# S7500_Drv.net
KiCad netlist of a schematic drawn in Altium Designer
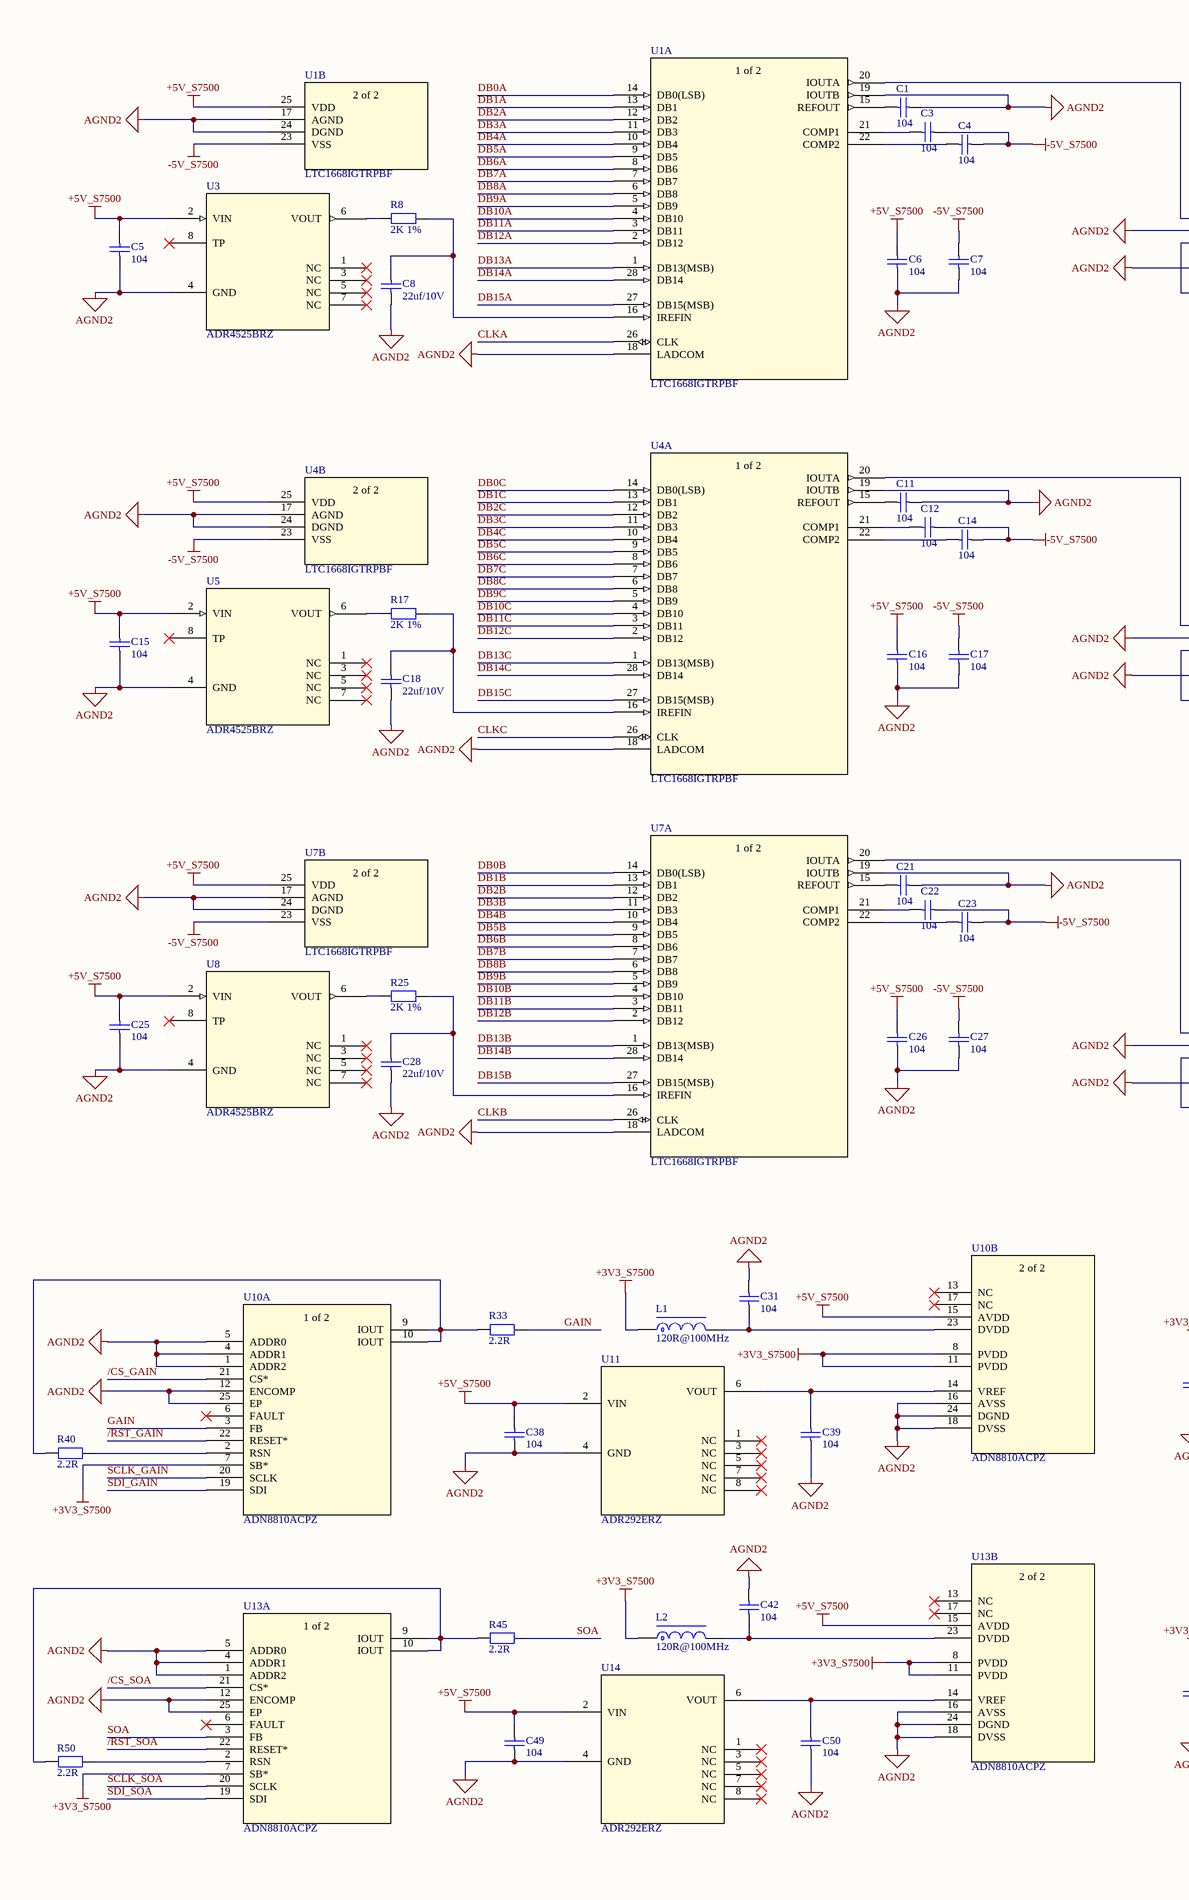
[diagram p0: S7500_Drv.SchDoc, left]
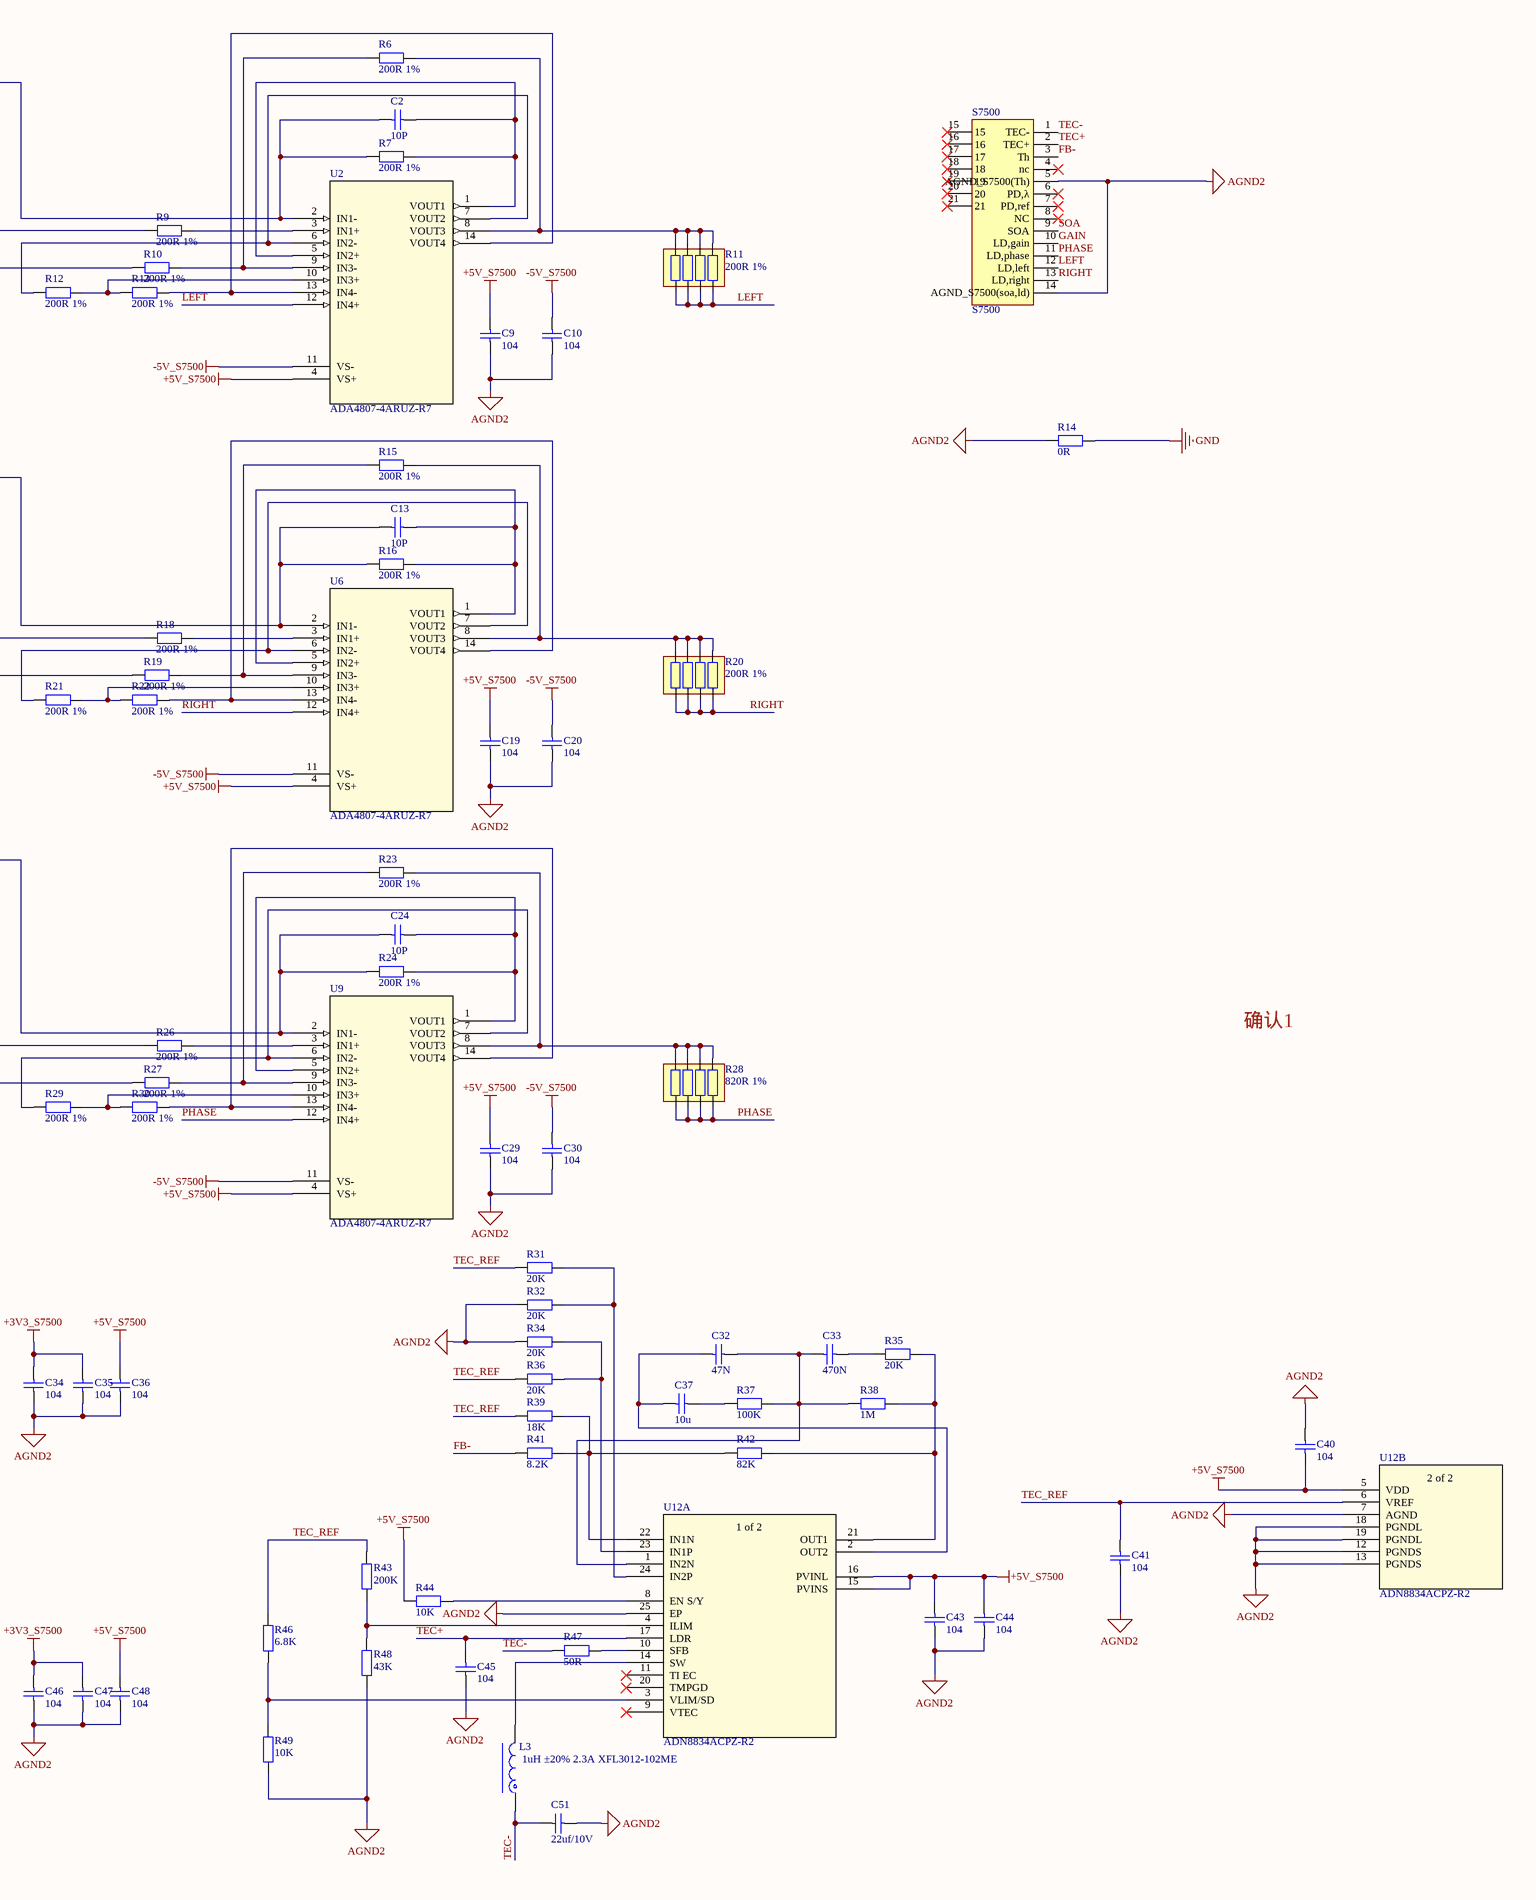
[diagram p1: S7500_Drv.SchDoc, right]

(export (version "E")
  (design (tool "Eeschema 10.0.6"))
  (components
    (comp (ref "C1")
      (value "104")
      (footprint "C0402_L")
      (description "贴片电容/MLCC电容")
      (libsource (lib "0.1 - 电阻-电容-电感-保险丝-晶振-晶体-磁珠-电位器-法拉电容-馈通电容") (part "C"))
    )
    (comp (ref "C2")
      (value "10P")
      (footprint "C0402_L")
      (description "贴片电容/MLCC电容")
      (libsource (lib "0.1 - 电阻-电容-电感-保险丝-晶振-晶体-磁珠-电位器-法拉电容-馈通电容") (part "C"))
    )
    (comp (ref "C3")
      (value "104")
      (footprint "C0402_L")
      (description "贴片电容/MLCC电容")
      (libsource (lib "0.1 - 电阻-电容-电感-保险丝-晶振-晶体-磁珠-电位器-法拉电容-馈通电容") (part "C"))
    )
    (comp (ref "C4")
      (value "104")
      (footprint "C0402_L")
      (description "贴片电容/MLCC电容")
      (libsource (lib "0.1 - 电阻-电容-电感-保险丝-晶振-晶体-磁珠-电位器-法拉电容-馈通电容") (part "C"))
    )
    (comp (ref "C5")
      (value "104")
      (footprint "C0402_L")
      (description "贴片电容/MLCC电容")
      (libsource (lib "0.1 - 电阻-电容-电感-保险丝-晶振-晶体-磁珠-电位器-法拉电容-馈通电容") (part "C"))
    )
    (comp (ref "C6")
      (value "104")
      (footprint "C0402_L")
      (description "贴片电容/MLCC电容")
      (libsource (lib "0.1 - 电阻-电容-电感-保险丝-晶振-晶体-磁珠-电位器-法拉电容-馈通电容") (part "C"))
    )
    (comp (ref "C7")
      (value "104")
      (footprint "C0402_L")
      (description "贴片电容/MLCC电容")
      (libsource (lib "0.1 - 电阻-电容-电感-保险丝-晶振-晶体-磁珠-电位器-法拉电容-馈通电容") (part "C"))
    )
    (comp (ref "C8")
      (value "22uf/10V")
      (footprint "C0402_L")
      (description "贴片电容/MLCC电容")
      (libsource (lib "0.1 - 电阻-电容-电感-保险丝-晶振-晶体-磁珠-电位器-法拉电容-馈通电容") (part "C"))
    )
    (comp (ref "C9")
      (value "104")
      (footprint "C0402_L")
      (description "贴片电容/MLCC电容")
      (libsource (lib "0.1 - 电阻-电容-电感-保险丝-晶振-晶体-磁珠-电位器-法拉电容-馈通电容") (part "C"))
    )
    (comp (ref "C10")
      (value "104")
      (footprint "C0402_L")
      (description "贴片电容/MLCC电容")
      (libsource (lib "0.1 - 电阻-电容-电感-保险丝-晶振-晶体-磁珠-电位器-法拉电容-馈通电容") (part "C"))
    )
    (comp (ref "C11")
      (value "104")
      (footprint "C0402_L")
      (description "贴片电容/MLCC电容")
      (libsource (lib "0.1 - 电阻-电容-电感-保险丝-晶振-晶体-磁珠-电位器-法拉电容-馈通电容") (part "C"))
    )
    (comp (ref "C12")
      (value "104")
      (footprint "C0402_L")
      (description "贴片电容/MLCC电容")
      (libsource (lib "0.1 - 电阻-电容-电感-保险丝-晶振-晶体-磁珠-电位器-法拉电容-馈通电容") (part "C"))
    )
    (comp (ref "C13")
      (value "10P")
      (footprint "C0402_L")
      (description "贴片电容/MLCC电容")
      (libsource (lib "0.1 - 电阻-电容-电感-保险丝-晶振-晶体-磁珠-电位器-法拉电容-馈通电容") (part "C"))
    )
    (comp (ref "C14")
      (value "104")
      (footprint "C0402_L")
      (description "贴片电容/MLCC电容")
      (libsource (lib "0.1 - 电阻-电容-电感-保险丝-晶振-晶体-磁珠-电位器-法拉电容-馈通电容") (part "C"))
    )
    (comp (ref "C15")
      (value "104")
      (footprint "C0402_L")
      (description "贴片电容/MLCC电容")
      (libsource (lib "0.1 - 电阻-电容-电感-保险丝-晶振-晶体-磁珠-电位器-法拉电容-馈通电容") (part "C"))
    )
    (comp (ref "C16")
      (value "104")
      (footprint "C0402_L")
      (description "贴片电容/MLCC电容")
      (libsource (lib "0.1 - 电阻-电容-电感-保险丝-晶振-晶体-磁珠-电位器-法拉电容-馈通电容") (part "C"))
    )
    (comp (ref "C17")
      (value "104")
      (footprint "C0402_L")
      (description "贴片电容/MLCC电容")
      (libsource (lib "0.1 - 电阻-电容-电感-保险丝-晶振-晶体-磁珠-电位器-法拉电容-馈通电容") (part "C"))
    )
    (comp (ref "C18")
      (value "22uf/10V")
      (footprint "C0402_L")
      (description "贴片电容/MLCC电容")
      (libsource (lib "0.1 - 电阻-电容-电感-保险丝-晶振-晶体-磁珠-电位器-法拉电容-馈通电容") (part "C"))
    )
    (comp (ref "C19")
      (value "104")
      (footprint "C0402_L")
      (description "贴片电容/MLCC电容")
      (libsource (lib "0.1 - 电阻-电容-电感-保险丝-晶振-晶体-磁珠-电位器-法拉电容-馈通电容") (part "C"))
    )
    (comp (ref "C20")
      (value "104")
      (footprint "C0402_L")
      (description "贴片电容/MLCC电容")
      (libsource (lib "0.1 - 电阻-电容-电感-保险丝-晶振-晶体-磁珠-电位器-法拉电容-馈通电容") (part "C"))
    )
    (comp (ref "C21")
      (value "104")
      (footprint "C0402_L")
      (description "贴片电容/MLCC电容")
      (libsource (lib "0.1 - 电阻-电容-电感-保险丝-晶振-晶体-磁珠-电位器-法拉电容-馈通电容") (part "C"))
    )
    (comp (ref "C22")
      (value "104")
      (footprint "C0402_L")
      (description "贴片电容/MLCC电容")
      (libsource (lib "0.1 - 电阻-电容-电感-保险丝-晶振-晶体-磁珠-电位器-法拉电容-馈通电容") (part "C"))
    )
    (comp (ref "C23")
      (value "104")
      (footprint "C0402_L")
      (description "贴片电容/MLCC电容")
      (libsource (lib "0.1 - 电阻-电容-电感-保险丝-晶振-晶体-磁珠-电位器-法拉电容-馈通电容") (part "C"))
    )
    (comp (ref "C24")
      (value "10P")
      (footprint "C0402_L")
      (description "贴片电容/MLCC电容")
      (libsource (lib "0.1 - 电阻-电容-电感-保险丝-晶振-晶体-磁珠-电位器-法拉电容-馈通电容") (part "C"))
    )
    (comp (ref "C25")
      (value "104")
      (footprint "C0402_L")
      (description "贴片电容/MLCC电容")
      (libsource (lib "0.1 - 电阻-电容-电感-保险丝-晶振-晶体-磁珠-电位器-法拉电容-馈通电容") (part "C"))
    )
    (comp (ref "C26")
      (value "104")
      (footprint "C0402_L")
      (description "贴片电容/MLCC电容")
      (libsource (lib "0.1 - 电阻-电容-电感-保险丝-晶振-晶体-磁珠-电位器-法拉电容-馈通电容") (part "C"))
    )
    (comp (ref "C27")
      (value "104")
      (footprint "C0402_L")
      (description "贴片电容/MLCC电容")
      (libsource (lib "0.1 - 电阻-电容-电感-保险丝-晶振-晶体-磁珠-电位器-法拉电容-馈通电容") (part "C"))
    )
    (comp (ref "C28")
      (value "22uf/10V")
      (footprint "C0402_L")
      (description "贴片电容/MLCC电容")
      (libsource (lib "0.1 - 电阻-电容-电感-保险丝-晶振-晶体-磁珠-电位器-法拉电容-馈通电容") (part "C"))
    )
    (comp (ref "C29")
      (value "104")
      (footprint "C0402_L")
      (description "贴片电容/MLCC电容")
      (libsource (lib "0.1 - 电阻-电容-电感-保险丝-晶振-晶体-磁珠-电位器-法拉电容-馈通电容") (part "C"))
    )
    (comp (ref "C30")
      (value "104")
      (footprint "C0402_L")
      (description "贴片电容/MLCC电容")
      (libsource (lib "0.1 - 电阻-电容-电感-保险丝-晶振-晶体-磁珠-电位器-法拉电容-馈通电容") (part "C"))
    )
    (comp (ref "C31")
      (value "104")
      (footprint "C0402_L")
      (description "贴片电容/MLCC电容")
      (libsource (lib "0.1 - 电阻-电容-电感-保险丝-晶振-晶体-磁珠-电位器-法拉电容-馈通电容") (part "C"))
    )
    (comp (ref "C32")
      (value "47N")
      (footprint "C0402_L")
      (description "贴片电容/MLCC电容")
      (libsource (lib "0.1 - 电阻-电容-电感-保险丝-晶振-晶体-磁珠-电位器-法拉电容-馈通电容") (part "C"))
    )
    (comp (ref "C33")
      (value "470N")
      (footprint "C0402_L")
      (description "贴片电容/MLCC电容")
      (libsource (lib "0.1 - 电阻-电容-电感-保险丝-晶振-晶体-磁珠-电位器-法拉电容-馈通电容") (part "C"))
    )
    (comp (ref "C34")
      (value "104")
      (footprint "C0402_L")
      (description "贴片电容/MLCC电容")
      (libsource (lib "0.1 - 电阻-电容-电感-保险丝-晶振-晶体-磁珠-电位器-法拉电容-馈通电容") (part "C"))
    )
    (comp (ref "C35")
      (value "104")
      (footprint "C0402_L")
      (description "贴片电容/MLCC电容")
      (libsource (lib "0.1 - 电阻-电容-电感-保险丝-晶振-晶体-磁珠-电位器-法拉电容-馈通电容") (part "C"))
    )
    (comp (ref "C36")
      (value "104")
      (footprint "C0402_L")
      (description "贴片电容/MLCC电容")
      (libsource (lib "0.1 - 电阻-电容-电感-保险丝-晶振-晶体-磁珠-电位器-法拉电容-馈通电容") (part "C"))
    )
    (comp (ref "C37")
      (value "10u")
      (footprint "C0402_L")
      (description "贴片电容/MLCC电容")
      (libsource (lib "0.1 - 电阻-电容-电感-保险丝-晶振-晶体-磁珠-电位器-法拉电容-馈通电容") (part "C"))
    )
    (comp (ref "C38")
      (value "104")
      (footprint "C0402_L")
      (description "贴片电容/MLCC电容")
      (libsource (lib "0.1 - 电阻-电容-电感-保险丝-晶振-晶体-磁珠-电位器-法拉电容-馈通电容") (part "C"))
    )
    (comp (ref "C39")
      (value "104")
      (footprint "C0402_L")
      (description "贴片电容/MLCC电容")
      (libsource (lib "0.1 - 电阻-电容-电感-保险丝-晶振-晶体-磁珠-电位器-法拉电容-馈通电容") (part "C"))
    )
    (comp (ref "C40")
      (value "104")
      (footprint "C0402_L")
      (description "贴片电容/MLCC电容")
      (libsource (lib "0.1 - 电阻-电容-电感-保险丝-晶振-晶体-磁珠-电位器-法拉电容-馈通电容") (part "C"))
    )
    (comp (ref "C41")
      (value "104")
      (footprint "C0402_L")
      (description "贴片电容/MLCC电容")
      (libsource (lib "0.1 - 电阻-电容-电感-保险丝-晶振-晶体-磁珠-电位器-法拉电容-馈通电容") (part "C"))
    )
    (comp (ref "C42")
      (value "104")
      (footprint "C0402_L")
      (description "贴片电容/MLCC电容")
      (libsource (lib "0.1 - 电阻-电容-电感-保险丝-晶振-晶体-磁珠-电位器-法拉电容-馈通电容") (part "C"))
    )
    (comp (ref "C43")
      (value "104")
      (footprint "C0402_L")
      (description "贴片电容/MLCC电容")
      (libsource (lib "0.1 - 电阻-电容-电感-保险丝-晶振-晶体-磁珠-电位器-法拉电容-馈通电容") (part "C"))
    )
    (comp (ref "C44")
      (value "104")
      (footprint "C0402_L")
      (description "贴片电容/MLCC电容")
      (libsource (lib "0.1 - 电阻-电容-电感-保险丝-晶振-晶体-磁珠-电位器-法拉电容-馈通电容") (part "C"))
    )
    (comp (ref "C45")
      (value "104")
      (footprint "C0402_L")
      (description "贴片电容/MLCC电容")
      (libsource (lib "0.1 - 电阻-电容-电感-保险丝-晶振-晶体-磁珠-电位器-法拉电容-馈通电容") (part "C"))
    )
    (comp (ref "C46")
      (value "104")
      (footprint "C0402_L")
      (description "贴片电容/MLCC电容")
      (libsource (lib "0.1 - 电阻-电容-电感-保险丝-晶振-晶体-磁珠-电位器-法拉电容-馈通电容") (part "C"))
    )
    (comp (ref "C47")
      (value "104")
      (footprint "C0402_L")
      (description "贴片电容/MLCC电容")
      (libsource (lib "0.1 - 电阻-电容-电感-保险丝-晶振-晶体-磁珠-电位器-法拉电容-馈通电容") (part "C"))
    )
    (comp (ref "C48")
      (value "104")
      (footprint "C0402_L")
      (description "贴片电容/MLCC电容")
      (libsource (lib "0.1 - 电阻-电容-电感-保险丝-晶振-晶体-磁珠-电位器-法拉电容-馈通电容") (part "C"))
    )
    (comp (ref "C49")
      (value "104")
      (footprint "C0402_L")
      (description "贴片电容/MLCC电容")
      (libsource (lib "0.1 - 电阻-电容-电感-保险丝-晶振-晶体-磁珠-电位器-法拉电容-馈通电容") (part "C"))
    )
    (comp (ref "C50")
      (value "104")
      (footprint "C0402_L")
      (description "贴片电容/MLCC电容")
      (libsource (lib "0.1 - 电阻-电容-电感-保险丝-晶振-晶体-磁珠-电位器-法拉电容-馈通电容") (part "C"))
    )
    (comp (ref "C51")
      (value "22uf/10V")
      (footprint "C0402_L")
      (description "贴片电容/MLCC电容")
      (libsource (lib "0.1 - 电阻-电容-电感-保险丝-晶振-晶体-磁珠-电位器-法拉电容-馈通电容") (part "C"))
    )
    (comp (ref "L1")
      (value "120R@100MHz")
      (footprint "FB0402")
      (description "贴片磁珠")
      (libsource (lib "0.1 - 电阻-电容-电感-保险丝-晶振-晶体-磁珠-电位器-法拉电容-馈通电容") (part "FB"))
    )
    (comp (ref "L2")
      (value "120R@100MHz")
      (footprint "FB0402")
      (description "贴片磁珠")
      (libsource (lib "0.1 - 电阻-电容-电感-保险丝-晶振-晶体-磁珠-电位器-法拉电容-馈通电容") (part "FB"))
    )
    (comp (ref "L3")
      (value "1uH ±20% 2.3A XFL3012-102ME")
      (footprint "SWPA3015")
      (description "顺络_SWPA贴片屏蔽电感")
      (libsource (lib "0.1 - 电阻-电容-电感-保险丝-晶振-晶体-磁珠-电位器-法拉电容-馈通电容") (part "L-SWPA"))
    )
    (comp (ref "R6")
      (value "200R 1%")
      (footprint "R0402_L")
      (description "贴片电阻")
      (libsource (lib "0.1 - 电阻-电容-电感-保险丝-晶振-晶体-磁珠-电位器-法拉电容-馈通电容") (part "R"))
    )
    (comp (ref "R7")
      (value "200R 1%")
      (footprint "R0402_L")
      (description "贴片电阻")
      (libsource (lib "0.1 - 电阻-电容-电感-保险丝-晶振-晶体-磁珠-电位器-法拉电容-馈通电容") (part "R"))
    )
    (comp (ref "R8")
      (value "2K 1%")
      (footprint "R0402_L")
      (description "贴片电阻")
      (libsource (lib "0.1 - 电阻-电容-电感-保险丝-晶振-晶体-磁珠-电位器-法拉电容-馈通电容") (part "R"))
    )
    (comp (ref "R9")
      (value "200R 1%")
      (footprint "R0402_L")
      (description "贴片电阻")
      (libsource (lib "0.1 - 电阻-电容-电感-保险丝-晶振-晶体-磁珠-电位器-法拉电容-馈通电容") (part "R"))
    )
    (comp (ref "R10")
      (value "200R 1%")
      (footprint "R0402_L")
      (description "贴片电阻")
      (libsource (lib "0.1 - 电阻-电容-电感-保险丝-晶振-晶体-磁珠-电位器-法拉电容-馈通电容") (part "R"))
    )
    (comp (ref "R11")
      (value "200R 1%")
      (footprint "RCA-8P4R-0603")
      (description "贴片4P排阻")
      (libsource (lib "0.1 - 电阻-电容-电感-保险丝-晶振-晶体-磁珠-电位器-法拉电容-馈通电容") (part "R-8P4R"))
    )
    (comp (ref "R12")
      (value "200R 1%")
      (footprint "R0402_L")
      (description "贴片电阻")
      (libsource (lib "0.1 - 电阻-电容-电感-保险丝-晶振-晶体-磁珠-电位器-法拉电容-馈通电容") (part "R"))
    )
    (comp (ref "R13")
      (value "200R 1%")
      (footprint "R0402_L")
      (description "贴片电阻")
      (libsource (lib "0.1 - 电阻-电容-电感-保险丝-晶振-晶体-磁珠-电位器-法拉电容-馈通电容") (part "R"))
    )
    (comp (ref "R14")
      (value "0R")
      (footprint "R0402_L")
      (description "贴片电阻")
      (libsource (lib "0.1 - 电阻-电容-电感-保险丝-晶振-晶体-磁珠-电位器-法拉电容-馈通电容") (part "R"))
    )
    (comp (ref "R15")
      (value "200R 1%")
      (footprint "R0402_L")
      (description "贴片电阻")
      (libsource (lib "0.1 - 电阻-电容-电感-保险丝-晶振-晶体-磁珠-电位器-法拉电容-馈通电容") (part "R"))
    )
    (comp (ref "R16")
      (value "200R 1%")
      (footprint "R0402_L")
      (description "贴片电阻")
      (libsource (lib "0.1 - 电阻-电容-电感-保险丝-晶振-晶体-磁珠-电位器-法拉电容-馈通电容") (part "R"))
    )
    (comp (ref "R17")
      (value "2K 1%")
      (footprint "R0402_L")
      (description "贴片电阻")
      (libsource (lib "0.1 - 电阻-电容-电感-保险丝-晶振-晶体-磁珠-电位器-法拉电容-馈通电容") (part "R"))
    )
    (comp (ref "R18")
      (value "200R 1%")
      (footprint "R0402_L")
      (description "贴片电阻")
      (libsource (lib "0.1 - 电阻-电容-电感-保险丝-晶振-晶体-磁珠-电位器-法拉电容-馈通电容") (part "R"))
    )
    (comp (ref "R19")
      (value "200R 1%")
      (footprint "R0402_L")
      (description "贴片电阻")
      (libsource (lib "0.1 - 电阻-电容-电感-保险丝-晶振-晶体-磁珠-电位器-法拉电容-馈通电容") (part "R"))
    )
    (comp (ref "R20")
      (value "200R 1%")
      (footprint "RCA-8P4R-0603")
      (description "贴片4P排阻")
      (libsource (lib "0.1 - 电阻-电容-电感-保险丝-晶振-晶体-磁珠-电位器-法拉电容-馈通电容") (part "R-8P4R"))
    )
    (comp (ref "R21")
      (value "200R 1%")
      (footprint "R0402_L")
      (description "贴片电阻")
      (libsource (lib "0.1 - 电阻-电容-电感-保险丝-晶振-晶体-磁珠-电位器-法拉电容-馈通电容") (part "R"))
    )
    (comp (ref "R22")
      (value "200R 1%")
      (footprint "R0402_L")
      (description "贴片电阻")
      (libsource (lib "0.1 - 电阻-电容-电感-保险丝-晶振-晶体-磁珠-电位器-法拉电容-馈通电容") (part "R"))
    )
    (comp (ref "R23")
      (value "200R 1%")
      (footprint "R0402_L")
      (description "贴片电阻")
      (libsource (lib "0.1 - 电阻-电容-电感-保险丝-晶振-晶体-磁珠-电位器-法拉电容-馈通电容") (part "R"))
    )
    (comp (ref "R24")
      (value "200R 1%")
      (footprint "R0402_L")
      (description "贴片电阻")
      (libsource (lib "0.1 - 电阻-电容-电感-保险丝-晶振-晶体-磁珠-电位器-法拉电容-馈通电容") (part "R"))
    )
    (comp (ref "R25")
      (value "2K 1%")
      (footprint "R0402_L")
      (description "贴片电阻")
      (libsource (lib "0.1 - 电阻-电容-电感-保险丝-晶振-晶体-磁珠-电位器-法拉电容-馈通电容") (part "R"))
    )
    (comp (ref "R26")
      (value "200R 1%")
      (footprint "R0402_L")
      (description "贴片电阻")
      (libsource (lib "0.1 - 电阻-电容-电感-保险丝-晶振-晶体-磁珠-电位器-法拉电容-馈通电容") (part "R"))
    )
    (comp (ref "R27")
      (value "200R 1%")
      (footprint "R0402_L")
      (description "贴片电阻")
      (libsource (lib "0.1 - 电阻-电容-电感-保险丝-晶振-晶体-磁珠-电位器-法拉电容-馈通电容") (part "R"))
    )
    (comp (ref "R28")
      (value "820R 1%")
      (footprint "RCA-8P4R-0603")
      (description "贴片4P排阻")
      (libsource (lib "0.1 - 电阻-电容-电感-保险丝-晶振-晶体-磁珠-电位器-法拉电容-馈通电容") (part "R-8P4R"))
    )
    (comp (ref "R29")
      (value "200R 1%")
      (footprint "R0402_L")
      (description "贴片电阻")
      (libsource (lib "0.1 - 电阻-电容-电感-保险丝-晶振-晶体-磁珠-电位器-法拉电容-馈通电容") (part "R"))
    )
    (comp (ref "R30")
      (value "200R 1%")
      (footprint "R0402_L")
      (description "贴片电阻")
      (libsource (lib "0.1 - 电阻-电容-电感-保险丝-晶振-晶体-磁珠-电位器-法拉电容-馈通电容") (part "R"))
    )
    (comp (ref "R31")
      (value "20K")
      (footprint "R0402_L")
      (description "贴片电阻")
      (libsource (lib "0.1 - 电阻-电容-电感-保险丝-晶振-晶体-磁珠-电位器-法拉电容-馈通电容") (part "R"))
    )
    (comp (ref "R32")
      (value "20K")
      (footprint "R0402_L")
      (description "贴片电阻")
      (libsource (lib "0.1 - 电阻-电容-电感-保险丝-晶振-晶体-磁珠-电位器-法拉电容-馈通电容") (part "R"))
    )
    (comp (ref "R33")
      (value "2.2R")
      (footprint "R0603_L")
      (description "贴片电阻")
      (libsource (lib "0.1 - 电阻-电容-电感-保险丝-晶振-晶体-磁珠-电位器-法拉电容-馈通电容") (part "R"))
    )
    (comp (ref "R34")
      (value "20K")
      (footprint "R0402_L")
      (description "贴片电阻")
      (libsource (lib "0.1 - 电阻-电容-电感-保险丝-晶振-晶体-磁珠-电位器-法拉电容-馈通电容") (part "R"))
    )
    (comp (ref "R35")
      (value "20K")
      (footprint "R0402_L")
      (description "贴片电阻")
      (libsource (lib "0.1 - 电阻-电容-电感-保险丝-晶振-晶体-磁珠-电位器-法拉电容-馈通电容") (part "R"))
    )
    (comp (ref "R36")
      (value "20K")
      (footprint "R0402_L")
      (description "贴片电阻")
      (libsource (lib "0.1 - 电阻-电容-电感-保险丝-晶振-晶体-磁珠-电位器-法拉电容-馈通电容") (part "R"))
    )
    (comp (ref "R37")
      (value "100K")
      (footprint "R0402_L")
      (description "贴片电阻")
      (libsource (lib "0.1 - 电阻-电容-电感-保险丝-晶振-晶体-磁珠-电位器-法拉电容-馈通电容") (part "R"))
    )
    (comp (ref "R38")
      (value "1M")
      (footprint "R0402_L")
      (description "贴片电阻")
      (libsource (lib "0.1 - 电阻-电容-电感-保险丝-晶振-晶体-磁珠-电位器-法拉电容-馈通电容") (part "R"))
    )
    (comp (ref "R39")
      (value "18K")
      (footprint "R0402_L")
      (description "贴片电阻")
      (libsource (lib "0.1 - 电阻-电容-电感-保险丝-晶振-晶体-磁珠-电位器-法拉电容-馈通电容") (part "R"))
    )
    (comp (ref "R40")
      (value "2.2R")
      (footprint "R0603_L")
      (description "贴片电阻")
      (libsource (lib "0.1 - 电阻-电容-电感-保险丝-晶振-晶体-磁珠-电位器-法拉电容-馈通电容") (part "R"))
    )
    (comp (ref "R41")
      (value "8.2K")
      (footprint "R0402_L")
      (description "贴片电阻")
      (libsource (lib "0.1 - 电阻-电容-电感-保险丝-晶振-晶体-磁珠-电位器-法拉电容-馈通电容") (part "R"))
    )
    (comp (ref "R42")
      (value "82K")
      (footprint "R0402_L")
      (description "贴片电阻")
      (libsource (lib "0.1 - 电阻-电容-电感-保险丝-晶振-晶体-磁珠-电位器-法拉电容-馈通电容") (part "R"))
    )
    (comp (ref "R43")
      (value "200K")
      (footprint "R0402_L")
      (description "贴片电阻")
      (libsource (lib "0.1 - 电阻-电容-电感-保险丝-晶振-晶体-磁珠-电位器-法拉电容-馈通电容") (part "R"))
    )
    (comp (ref "R44")
      (value "10K")
      (footprint "R0402_L")
      (description "贴片电阻")
      (libsource (lib "0.1 - 电阻-电容-电感-保险丝-晶振-晶体-磁珠-电位器-法拉电容-馈通电容") (part "R"))
    )
    (comp (ref "R45")
      (value "2.2R")
      (footprint "R0603_L")
      (description "贴片电阻")
      (libsource (lib "0.1 - 电阻-电容-电感-保险丝-晶振-晶体-磁珠-电位器-法拉电容-馈通电容") (part "R"))
    )
    (comp (ref "R46")
      (value "6.8K")
      (footprint "R0402_L")
      (description "贴片电阻")
      (libsource (lib "0.1 - 电阻-电容-电感-保险丝-晶振-晶体-磁珠-电位器-法拉电容-馈通电容") (part "R"))
    )
    (comp (ref "R47")
      (value "50R")
      (footprint "R0402_L")
      (description "贴片电阻")
      (libsource (lib "0.1 - 电阻-电容-电感-保险丝-晶振-晶体-磁珠-电位器-法拉电容-馈通电容") (part "R"))
    )
    (comp (ref "R48")
      (value "43K")
      (footprint "R0402_L")
      (description "贴片电阻")
      (libsource (lib "0.1 - 电阻-电容-电感-保险丝-晶振-晶体-磁珠-电位器-法拉电容-馈通电容") (part "R"))
    )
    (comp (ref "R49")
      (value "10K")
      (footprint "R0402_L")
      (description "贴片电阻")
      (libsource (lib "0.1 - 电阻-电容-电感-保险丝-晶振-晶体-磁珠-电位器-法拉电容-馈通电容") (part "R"))
    )
    (comp (ref "R50")
      (value "2.2R")
      (footprint "R0603_L")
      (description "贴片电阻")
      (libsource (lib "0.1 - 电阻-电容-电感-保险丝-晶振-晶体-磁珠-电位器-法拉电容-馈通电容") (part "R"))
    )
    (comp (ref "S7500")
      (value "S7500")
      (footprint "S7500-14*0.8mm")
      (libsource (lib "PCB_Project") (part "S7500"))
    )
    (comp (ref "U1")
      (value "LTC1668IGTRPBF")
      (footprint "SSOP-28_G_LIT")
      (description "No Description Available")
      (libsource (lib "LTC1668IGTRPBF") (part "LTC1668IGTRPBF"))
    )
    (comp (ref "U2")
      (value "ADA4807-4ARUZ-R7")
      (footprint "RU-14_ADI")
      (description "No Description Available")
      (libsource (lib "ADA4807-4ARUZ-R7") (part "ADA4807-4ARUZ-R7"))
    )
    (comp (ref "U3")
      (value "ADR4525BRZ")
      (footprint "R_8_ADI")
      (description "No Description Available")
      (libsource (lib "ADR4525BRZ") (part "ADR4525BRZ"))
    )
    (comp (ref "U4")
      (value "LTC1668IGTRPBF")
      (footprint "SSOP-28_G_LIT")
      (description "No Description Available")
      (libsource (lib "LTC1668IGTRPBF") (part "LTC1668IGTRPBF"))
    )
    (comp (ref "U5")
      (value "ADR4525BRZ")
      (footprint "R_8_ADI")
      (description "No Description Available")
      (libsource (lib "ADR4525BRZ") (part "ADR4525BRZ"))
    )
    (comp (ref "U6")
      (value "ADA4807-4ARUZ-R7")
      (footprint "RU-14_ADI")
      (description "No Description Available")
      (libsource (lib "ADA4807-4ARUZ-R7") (part "ADA4807-4ARUZ-R7"))
    )
    (comp (ref "U7")
      (value "LTC1668IGTRPBF")
      (footprint "SSOP-28_G_LIT")
      (description "No Description Available")
      (libsource (lib "LTC1668IGTRPBF") (part "LTC1668IGTRPBF"))
    )
    (comp (ref "U8")
      (value "ADR4525BRZ")
      (footprint "R_8_ADI")
      (description "No Description Available")
      (libsource (lib "ADR4525BRZ") (part "ADR4525BRZ"))
    )
    (comp (ref "U9")
      (value "ADA4807-4ARUZ-R7")
      (footprint "RU-14_ADI")
      (description "No Description Available")
      (libsource (lib "ADA4807-4ARUZ-R7") (part "ADA4807-4ARUZ-R7"))
    )
    (comp (ref "U10")
      (value "ADN8810ACPZ")
      (footprint "CP_24_1_ADI")
      (description "No Description Available")
      (libsource (lib "ADN8810ACPZ") (part "ADN8810ACPZ"))
    )
    (comp (ref "U11")
      (value "ADR292ERZ")
      (footprint "R_8_ADI")
      (description "No Description Available")
      (libsource (lib "ADR292ERZ") (part "ADR292ERZ"))
    )
    (comp (ref "U12")
      (value "ADN8834ACPZ-R2")
      (footprint "CP_24_7_ADI")
      (description "No Description Available")
      (libsource (lib "ADN8834ACPZ-R2") (part "ADN8834ACPZ-R2"))
    )
    (comp (ref "U13")
      (value "ADN8810ACPZ")
      (footprint "CP_24_1_ADI")
      (description "No Description Available")
      (libsource (lib "ADN8810ACPZ") (part "ADN8810ACPZ"))
    )
    (comp (ref "U14")
      (value "ADR292ERZ")
      (footprint "R_8_ADI")
      (description "No Description Available")
      (libsource (lib "ADR292ERZ") (part "ADR292ERZ"))
    )
  )
  (nets
    (net (code "1") (name "+3V3_S7500") (class "Default")
      (node (ref "C34") (pin "2") (pinfunction "2_2") (pintype "passive"))
      (node (ref "C35") (pin "2") (pinfunction "2_2") (pintype "passive"))
      (node (ref "C46") (pin "2") (pinfunction "2_2") (pintype "passive"))
      (node (ref "C47") (pin "2") (pinfunction "2_2") (pintype "passive"))
      (node (ref "L1") (pin "1") (pinfunction "1_1") (pintype "passive"))
      (node (ref "L2") (pin "1") (pinfunction "1_1") (pintype "passive"))
      (node (ref "U10") (pin "11") (pinfunction "PVDD_11") (pintype "power_in"))
      (node (ref "U10") (pin "7") (pinfunction "SB*_7") (pintype "passive"))
      (node (ref "U10") (pin "8") (pinfunction "PVDD_8") (pintype "power_in"))
      (node (ref "U13") (pin "11") (pinfunction "PVDD_11") (pintype "power_in"))
      (node (ref "U13") (pin "7") (pinfunction "SB*_7") (pintype "passive"))
      (node (ref "U13") (pin "8") (pinfunction "PVDD_8") (pintype "power_in"))
    )
    (net (code "2") (name "+5V_S7500") (class "Default")
      (node (ref "C15") (pin "2") (pinfunction "2_2") (pintype "passive"))
      (node (ref "C16") (pin "2") (pinfunction "2_2") (pintype "passive"))
      (node (ref "C19") (pin "2") (pinfunction "2_2") (pintype "passive"))
      (node (ref "C25") (pin "2") (pinfunction "2_2") (pintype "passive"))
      (node (ref "C26") (pin "2") (pinfunction "2_2") (pintype "passive"))
      (node (ref "C29") (pin "2") (pinfunction "2_2") (pintype "passive"))
      (node (ref "C36") (pin "2") (pinfunction "2_2") (pintype "passive"))
      (node (ref "C38") (pin "2") (pinfunction "2_2") (pintype "passive"))
      (node (ref "C40") (pin "1") (pinfunction "1_1") (pintype "passive"))
      (node (ref "C43") (pin "2") (pinfunction "2_2") (pintype "passive"))
      (node (ref "C44") (pin "2") (pinfunction "2_2") (pintype "passive"))
      (node (ref "C48") (pin "2") (pinfunction "2_2") (pintype "passive"))
      (node (ref "C49") (pin "2") (pinfunction "2_2") (pintype "passive"))
      (node (ref "C5") (pin "2") (pinfunction "2_2") (pintype "passive"))
      (node (ref "C6") (pin "2") (pinfunction "2_2") (pintype "passive"))
      (node (ref "C9") (pin "2") (pinfunction "2_2") (pintype "passive"))
      (node (ref "R44") (pin "1") (pinfunction "1_1") (pintype "passive"))
      (node (ref "U1") (pin "25") (pinfunction "VDD_25") (pintype "power_in"))
      (node (ref "U10") (pin "15") (pinfunction "AVDD_15") (pintype "power_in"))
      (node (ref "U11") (pin "2") (pinfunction "VIN_2") (pintype "passive"))
      (node (ref "U12") (pin "15") (pinfunction "PVINS_15") (pintype "passive"))
      (node (ref "U12") (pin "16") (pinfunction "PVINL_16") (pintype "passive"))
      (node (ref "U12") (pin "5") (pinfunction "VDD_5") (pintype "passive"))
      (node (ref "U13") (pin "15") (pinfunction "AVDD_15") (pintype "power_in"))
      (node (ref "U14") (pin "2") (pinfunction "VIN_2") (pintype "passive"))
      (node (ref "U2") (pin "4") (pinfunction "VS+_4") (pintype "power_in"))
      (node (ref "U3") (pin "2") (pinfunction "VIN_2") (pintype "input"))
      (node (ref "U4") (pin "25") (pinfunction "VDD_25") (pintype "power_in"))
      (node (ref "U5") (pin "2") (pinfunction "VIN_2") (pintype "input"))
      (node (ref "U6") (pin "4") (pinfunction "VS+_4") (pintype "power_in"))
      (node (ref "U7") (pin "25") (pinfunction "VDD_25") (pintype "power_in"))
      (node (ref "U8") (pin "2") (pinfunction "VIN_2") (pintype "input"))
      (node (ref "U9") (pin "4") (pinfunction "VS+_4") (pintype "power_in"))
    )
    (net (code "3") (name "-5V_S7500") (class "Default")
      (node (ref "C10") (pin "2") (pinfunction "2_2") (pintype "passive"))
      (node (ref "C12") (pin "2") (pinfunction "2_2") (pintype "passive"))
      (node (ref "C14") (pin "2") (pinfunction "2_2") (pintype "passive"))
      (node (ref "C17") (pin "2") (pinfunction "2_2") (pintype "passive"))
      (node (ref "C20") (pin "2") (pinfunction "2_2") (pintype "passive"))
      (node (ref "C22") (pin "2") (pinfunction "2_2") (pintype "passive"))
      (node (ref "C23") (pin "2") (pinfunction "2_2") (pintype "passive"))
      (node (ref "C27") (pin "2") (pinfunction "2_2") (pintype "passive"))
      (node (ref "C3") (pin "2") (pinfunction "2_2") (pintype "passive"))
      (node (ref "C30") (pin "2") (pinfunction "2_2") (pintype "passive"))
      (node (ref "C4") (pin "2") (pinfunction "2_2") (pintype "passive"))
      (node (ref "C7") (pin "2") (pinfunction "2_2") (pintype "passive"))
      (node (ref "U1") (pin "23") (pinfunction "VSS_23") (pintype "power_in"))
      (node (ref "U2") (pin "11") (pinfunction "VS-_11") (pintype "power_in"))
      (node (ref "U4") (pin "23") (pinfunction "VSS_23") (pintype "power_in"))
      (node (ref "U6") (pin "11") (pinfunction "VS-_11") (pintype "power_in"))
      (node (ref "U7") (pin "23") (pinfunction "VSS_23") (pintype "power_in"))
      (node (ref "U9") (pin "11") (pinfunction "VS-_11") (pintype "power_in"))
    )
    (net (code "4") (name "/CLKA") (class "Default")
      (node (ref "U1") (pin "26") (pinfunction "CLK_26") (pintype "bidirectional"))
    )
    (net (code "5") (name "/CLKB") (class "Default")
      (node (ref "U7") (pin "26") (pinfunction "CLK_26") (pintype "bidirectional"))
    )
    (net (code "6") (name "/CLKC") (class "Default")
      (node (ref "U4") (pin "26") (pinfunction "CLK_26") (pintype "bidirectional"))
    )
    (net (code "7") (name "/DB0A") (class "Default")
      (node (ref "U1") (pin "14") (pinfunction "DB0(LSB)_14") (pintype "input"))
    )
    (net (code "8") (name "/DB0B") (class "Default")
      (node (ref "U7") (pin "14") (pinfunction "DB0(LSB)_14") (pintype "input"))
    )
    (net (code "9") (name "/DB0C") (class "Default")
      (node (ref "U4") (pin "14") (pinfunction "DB0(LSB)_14") (pintype "input"))
    )
    (net (code "10") (name "/DB1A") (class "Default")
      (node (ref "U1") (pin "13") (pinfunction "DB1_13") (pintype "input"))
    )
    (net (code "11") (name "/DB1B") (class "Default")
      (node (ref "U7") (pin "13") (pinfunction "DB1_13") (pintype "input"))
    )
    (net (code "12") (name "/DB1C") (class "Default")
      (node (ref "U4") (pin "13") (pinfunction "DB1_13") (pintype "input"))
    )
    (net (code "13") (name "/DB2A") (class "Default")
      (node (ref "U1") (pin "12") (pinfunction "DB2_12") (pintype "input"))
    )
    (net (code "14") (name "/DB2B") (class "Default")
      (node (ref "U7") (pin "12") (pinfunction "DB2_12") (pintype "input"))
    )
    (net (code "15") (name "/DB2C") (class "Default")
      (node (ref "U4") (pin "12") (pinfunction "DB2_12") (pintype "input"))
    )
    (net (code "16") (name "/DB3A") (class "Default")
      (node (ref "U1") (pin "11") (pinfunction "DB3_11") (pintype "input"))
    )
    (net (code "17") (name "/DB3B") (class "Default")
      (node (ref "U7") (pin "11") (pinfunction "DB3_11") (pintype "input"))
    )
    (net (code "18") (name "/DB3C") (class "Default")
      (node (ref "U4") (pin "11") (pinfunction "DB3_11") (pintype "input"))
    )
    (net (code "19") (name "/DB4A") (class "Default")
      (node (ref "U1") (pin "10") (pinfunction "DB4_10") (pintype "input"))
    )
    (net (code "20") (name "/DB4B") (class "Default")
      (node (ref "U7") (pin "10") (pinfunction "DB4_10") (pintype "input"))
    )
    (net (code "21") (name "/DB4C") (class "Default")
      (node (ref "U4") (pin "10") (pinfunction "DB4_10") (pintype "input"))
    )
    (net (code "22") (name "/DB5A") (class "Default")
      (node (ref "U1") (pin "9") (pinfunction "DB5_9") (pintype "input"))
    )
    (net (code "23") (name "/DB5B") (class "Default")
      (node (ref "U7") (pin "9") (pinfunction "DB5_9") (pintype "input"))
    )
    (net (code "24") (name "/DB5C") (class "Default")
      (node (ref "U4") (pin "9") (pinfunction "DB5_9") (pintype "input"))
    )
    (net (code "25") (name "/DB6A") (class "Default")
      (node (ref "U1") (pin "8") (pinfunction "DB6_8") (pintype "input"))
    )
    (net (code "26") (name "/DB6B") (class "Default")
      (node (ref "U7") (pin "8") (pinfunction "DB6_8") (pintype "input"))
    )
    (net (code "27") (name "/DB6C") (class "Default")
      (node (ref "U4") (pin "8") (pinfunction "DB6_8") (pintype "input"))
    )
    (net (code "28") (name "/DB7A") (class "Default")
      (node (ref "U1") (pin "7") (pinfunction "DB7_7") (pintype "input"))
    )
    (net (code "29") (name "/DB7B") (class "Default")
      (node (ref "U7") (pin "7") (pinfunction "DB7_7") (pintype "input"))
    )
    (net (code "30") (name "/DB7C") (class "Default")
      (node (ref "U4") (pin "7") (pinfunction "DB7_7") (pintype "input"))
    )
    (net (code "31") (name "/DB8A") (class "Default")
      (node (ref "U1") (pin "6") (pinfunction "DB8_6") (pintype "input"))
    )
    (net (code "32") (name "/DB8B") (class "Default")
      (node (ref "U7") (pin "6") (pinfunction "DB8_6") (pintype "input"))
    )
    (net (code "33") (name "/DB8C") (class "Default")
      (node (ref "U4") (pin "6") (pinfunction "DB8_6") (pintype "input"))
    )
    (net (code "34") (name "/DB9A") (class "Default")
      (node (ref "U1") (pin "5") (pinfunction "DB9_5") (pintype "input"))
    )
    (net (code "35") (name "/DB9B") (class "Default")
      (node (ref "U7") (pin "5") (pinfunction "DB9_5") (pintype "input"))
    )
    (net (code "36") (name "/DB9C") (class "Default")
      (node (ref "U4") (pin "5") (pinfunction "DB9_5") (pintype "input"))
    )
    (net (code "37") (name "/DB10A") (class "Default")
      (node (ref "U1") (pin "4") (pinfunction "DB10_4") (pintype "input"))
    )
    (net (code "38") (name "/DB10B") (class "Default")
      (node (ref "U7") (pin "4") (pinfunction "DB10_4") (pintype "input"))
    )
    (net (code "39") (name "/DB10C") (class "Default")
      (node (ref "U4") (pin "4") (pinfunction "DB10_4") (pintype "input"))
    )
    (net (code "40") (name "/DB11A") (class "Default")
      (node (ref "U1") (pin "3") (pinfunction "DB11_3") (pintype "input"))
    )
    (net (code "41") (name "/DB11B") (class "Default")
      (node (ref "U7") (pin "3") (pinfunction "DB11_3") (pintype "input"))
    )
    (net (code "42") (name "/DB11C") (class "Default")
      (node (ref "U4") (pin "3") (pinfunction "DB11_3") (pintype "input"))
    )
    (net (code "43") (name "/DB12A") (class "Default")
      (node (ref "U1") (pin "2") (pinfunction "DB12_2") (pintype "input"))
    )
    (net (code "44") (name "/DB12B") (class "Default")
      (node (ref "U7") (pin "2") (pinfunction "DB12_2") (pintype "input"))
    )
    (net (code "45") (name "/DB12C") (class "Default")
      (node (ref "U4") (pin "2") (pinfunction "DB12_2") (pintype "input"))
    )
    (net (code "46") (name "/DB13A") (class "Default")
      (node (ref "U1") (pin "1") (pinfunction "DB13(MSB)_1") (pintype "input"))
    )
    (net (code "47") (name "/DB13B") (class "Default")
      (node (ref "U7") (pin "1") (pinfunction "DB13(MSB)_1") (pintype "input"))
    )
    (net (code "48") (name "/DB13C") (class "Default")
      (node (ref "U4") (pin "1") (pinfunction "DB13(MSB)_1") (pintype "input"))
    )
    (net (code "49") (name "/DB14A") (class "Default")
      (node (ref "U1") (pin "28") (pinfunction "DB14_28") (pintype "input"))
    )
    (net (code "50") (name "/DB14B") (class "Default")
      (node (ref "U7") (pin "28") (pinfunction "DB14_28") (pintype "input"))
    )
    (net (code "51") (name "/DB14C") (class "Default")
      (node (ref "U4") (pin "28") (pinfunction "DB14_28") (pintype "input"))
    )
    (net (code "52") (name "/DB15A") (class "Default")
      (node (ref "U1") (pin "27") (pinfunction "DB15(MSB)_27") (pintype "input"))
    )
    (net (code "53") (name "/DB15B") (class "Default")
      (node (ref "U7") (pin "27") (pinfunction "DB15(MSB)_27") (pintype "input"))
    )
    (net (code "54") (name "/DB15C") (class "Default")
      (node (ref "U4") (pin "27") (pinfunction "DB15(MSB)_27") (pintype "input"))
    )
    (net (code "55") (name "/FB-") (class "Default")
      (node (ref "R41") (pin "1") (pinfunction "1_1") (pintype "passive"))
      (node (ref "S7500") (pin "3") (pinfunction "Th_3") (pintype "passive"))
    )
    (net (code "56") (name "/GAIN") (class "Default")
      (node (ref "R33") (pin "2") (pinfunction "2_2") (pintype "passive"))
      (node (ref "S7500") (pin "10") (pinfunction "LD,gain_10") (pintype "passive"))
      (node (ref "U10") (pin "3") (pinfunction "FB_3") (pintype "passive"))
    )
    (net (code "57") (name "/LEFT") (class "Default")
      (node (ref "R11") (pin "1") (pinfunction "1_1") (pintype "passive"))
      (node (ref "R11") (pin "2") (pinfunction "2_2") (pintype "passive"))
      (node (ref "R11") (pin "3") (pinfunction "3_3") (pintype "passive"))
      (node (ref "R11") (pin "4") (pinfunction "4_4") (pintype "passive"))
      (node (ref "S7500") (pin "12") (pinfunction "LD,left_12") (pintype "passive"))
      (node (ref "U2") (pin "12") (pinfunction "IN4+_12") (pintype "input"))
    )
    (net (code "58") (name "/PHASE") (class "Default")
      (node (ref "R28") (pin "1") (pinfunction "1_1") (pintype "passive"))
      (node (ref "R28") (pin "2") (pinfunction "2_2") (pintype "passive"))
      (node (ref "R28") (pin "3") (pinfunction "3_3") (pintype "passive"))
      (node (ref "R28") (pin "4") (pinfunction "4_4") (pintype "passive"))
      (node (ref "S7500") (pin "11") (pinfunction "LD,phase_11") (pintype "passive"))
      (node (ref "U9") (pin "12") (pinfunction "IN4+_12") (pintype "input"))
    )
    (net (code "59") (name "/RIGHT") (class "Default")
      (node (ref "R20") (pin "1") (pinfunction "1_1") (pintype "passive"))
      (node (ref "R20") (pin "2") (pinfunction "2_2") (pintype "passive"))
      (node (ref "R20") (pin "3") (pinfunction "3_3") (pintype "passive"))
      (node (ref "R20") (pin "4") (pinfunction "4_4") (pintype "passive"))
      (node (ref "S7500") (pin "13") (pinfunction "LD,right_13") (pintype "passive"))
      (node (ref "U6") (pin "12") (pinfunction "IN4+_12") (pintype "input"))
    )
    (net (code "60") (name "/SCLK_GAIN") (class "Default")
      (node (ref "U10") (pin "20") (pinfunction "SCLK_20") (pintype "passive"))
    )
    (net (code "61") (name "/SCLK_SOA") (class "Default")
      (node (ref "U13") (pin "20") (pinfunction "SCLK_20") (pintype "passive"))
    )
    (net (code "62") (name "/SDI_GAIN") (class "Default")
      (node (ref "U10") (pin "19") (pinfunction "SDI_19") (pintype "passive"))
    )
    (net (code "63") (name "/SDI_SOA") (class "Default")
      (node (ref "U13") (pin "19") (pinfunction "SDI_19") (pintype "passive"))
    )
    (net (code "64") (name "/SOA") (class "Default")
      (node (ref "R45") (pin "2") (pinfunction "2_2") (pintype "passive"))
      (node (ref "S7500") (pin "9") (pinfunction "SOA_9") (pintype "passive"))
      (node (ref "U13") (pin "3") (pinfunction "FB_3") (pintype "passive"))
    )
    (net (code "65") (name "/TEC+") (class "Default")
      (node (ref "C45") (pin "2") (pinfunction "2_2") (pintype "passive"))
      (node (ref "S7500") (pin "2") (pinfunction "TEC+_2") (pintype "passive"))
      (node (ref "U12") (pin "17") (pinfunction "LDR_17") (pintype "passive"))
    )
    (net (code "66") (name "/TEC-") (class "Default")
      (node (ref "C51") (pin "2") (pinfunction "2_2") (pintype "passive"))
      (node (ref "L3") (pin "1") (pinfunction "1_1") (pintype "passive"))
      (node (ref "R47") (pin "1") (pinfunction "1_1") (pintype "passive"))
      (node (ref "S7500") (pin "1") (pinfunction "TEC-_1") (pintype "passive"))
    )
    (net (code "67") (name "/TEC_REF") (class "Default")
      (node (ref "C41") (pin "2") (pinfunction "2_2") (pintype "passive"))
      (node (ref "R31") (pin "1") (pinfunction "1_1") (pintype "passive"))
      (node (ref "R36") (pin "1") (pinfunction "1_1") (pintype "passive"))
      (node (ref "R39") (pin "1") (pinfunction "1_1") (pintype "passive"))
      (node (ref "R43") (pin "2") (pinfunction "2_2") (pintype "passive"))
      (node (ref "R46") (pin "2") (pinfunction "2_2") (pintype "passive"))
      (node (ref "U12") (pin "6") (pinfunction "VREF_6") (pintype "passive"))
    )
    (net (code "68") (name "/{slash}CS_GAIN") (class "Default")
      (node (ref "U10") (pin "21") (pinfunction "CS*_21") (pintype "passive"))
    )
    (net (code "69") (name "/{slash}CS_SOA") (class "Default")
      (node (ref "U13") (pin "21") (pinfunction "CS*_21") (pintype "passive"))
    )
    (net (code "70") (name "/{slash}RST_GAIN") (class "Default")
      (node (ref "U10") (pin "22") (pinfunction "RESET*_22") (pintype "passive"))
    )
    (net (code "71") (name "/{slash}RST_SOA") (class "Default")
      (node (ref "U13") (pin "22") (pinfunction "RESET*_22") (pintype "passive"))
    )
    (net (code "72") (name "AGND2") (class "Default")
      (node (ref "C1") (pin "2") (pinfunction "2_2") (pintype "passive"))
      (node (ref "C10") (pin "1") (pinfunction "1_1") (pintype "passive"))
      (node (ref "C11") (pin "2") (pinfunction "2_2") (pintype "passive"))
      (node (ref "C15") (pin "1") (pinfunction "1_1") (pintype "passive"))
      (node (ref "C16") (pin "1") (pinfunction "1_1") (pintype "passive"))
      (node (ref "C17") (pin "1") (pinfunction "1_1") (pintype "passive"))
      (node (ref "C18") (pin "1") (pinfunction "1_1") (pintype "passive"))
      (node (ref "C19") (pin "1") (pinfunction "1_1") (pintype "passive"))
      (node (ref "C20") (pin "1") (pinfunction "1_1") (pintype "passive"))
      (node (ref "C21") (pin "2") (pinfunction "2_2") (pintype "passive"))
      (node (ref "C25") (pin "1") (pinfunction "1_1") (pintype "passive"))
      (node (ref "C26") (pin "1") (pinfunction "1_1") (pintype "passive"))
      (node (ref "C27") (pin "1") (pinfunction "1_1") (pintype "passive"))
      (node (ref "C28") (pin "1") (pinfunction "1_1") (pintype "passive"))
      (node (ref "C29") (pin "1") (pinfunction "1_1") (pintype "passive"))
      (node (ref "C30") (pin "1") (pinfunction "1_1") (pintype "passive"))
      (node (ref "C31") (pin "2") (pinfunction "2_2") (pintype "passive"))
      (node (ref "C34") (pin "1") (pinfunction "1_1") (pintype "passive"))
      (node (ref "C35") (pin "1") (pinfunction "1_1") (pintype "passive"))
      (node (ref "C36") (pin "1") (pinfunction "1_1") (pintype "passive"))
      (node (ref "C38") (pin "1") (pinfunction "1_1") (pintype "passive"))
      (node (ref "C39") (pin "1") (pinfunction "1_1") (pintype "passive"))
      (node (ref "C40") (pin "2") (pinfunction "2_2") (pintype "passive"))
      (node (ref "C41") (pin "1") (pinfunction "1_1") (pintype "passive"))
      (node (ref "C42") (pin "2") (pinfunction "2_2") (pintype "passive"))
      (node (ref "C43") (pin "1") (pinfunction "1_1") (pintype "passive"))
      (node (ref "C44") (pin "1") (pinfunction "1_1") (pintype "passive"))
      (node (ref "C45") (pin "1") (pinfunction "1_1") (pintype "passive"))
      (node (ref "C46") (pin "1") (pinfunction "1_1") (pintype "passive"))
      (node (ref "C47") (pin "1") (pinfunction "1_1") (pintype "passive"))
      (node (ref "C48") (pin "1") (pinfunction "1_1") (pintype "passive"))
      (node (ref "C49") (pin "1") (pinfunction "1_1") (pintype "passive"))
      (node (ref "C5") (pin "1") (pinfunction "1_1") (pintype "passive"))
      (node (ref "C50") (pin "1") (pinfunction "1_1") (pintype "passive"))
      (node (ref "C51") (pin "1") (pinfunction "1_1") (pintype "passive"))
      (node (ref "C6") (pin "1") (pinfunction "1_1") (pintype "passive"))
      (node (ref "C7") (pin "1") (pinfunction "1_1") (pintype "passive"))
      (node (ref "C8") (pin "1") (pinfunction "1_1") (pintype "passive"))
      (node (ref "C9") (pin "1") (pinfunction "1_1") (pintype "passive"))
      (node (ref "R10") (pin "1") (pinfunction "1_1") (pintype "passive"))
      (node (ref "R14") (pin "1") (pinfunction "1_1") (pintype "passive"))
      (node (ref "R18") (pin "1") (pinfunction "1_1") (pintype "passive"))
      (node (ref "R19") (pin "1") (pinfunction "1_1") (pintype "passive"))
      (node (ref "R26") (pin "1") (pinfunction "1_1") (pintype "passive"))
      (node (ref "R27") (pin "1") (pinfunction "1_1") (pintype "passive"))
      (node (ref "R32") (pin "1") (pinfunction "1_1") (pintype "passive"))
      (node (ref "R34") (pin "1") (pinfunction "1_1") (pintype "passive"))
      (node (ref "R48") (pin "1") (pinfunction "1_1") (pintype "passive"))
      (node (ref "R49") (pin "1") (pinfunction "1_1") (pintype "passive"))
      (node (ref "R9") (pin "1") (pinfunction "1_1") (pintype "passive"))
      (node (ref "S7500") (pin "14") (pinfunction "AGND_S7500(soa,ld)_14") (pintype "passive"))
      (node (ref "S7500") (pin "5") (pinfunction "AGND_S7500(Th)_5") (pintype "passive"))
      (node (ref "U1") (pin "17") (pinfunction "AGND_17") (pintype "power_in"))
      (node (ref "U1") (pin "18") (pinfunction "LADCOM_18") (pintype "passive"))
      (node (ref "U1") (pin "19") (pinfunction "IOUTB_19") (pintype "output"))
      (node (ref "U1") (pin "24") (pinfunction "DGND_24") (pintype "power_in"))
      (node (ref "U10") (pin "1") (pinfunction "ADDR2_1") (pintype "passive"))
      (node (ref "U10") (pin "12") (pinfunction "ENCOMP_12") (pintype "passive"))
      (node (ref "U10") (pin "16") (pinfunction "AVSS_16") (pintype "passive"))
      (node (ref "U10") (pin "18") (pinfunction "DVSS_18") (pintype "passive"))
      (node (ref "U10") (pin "24") (pinfunction "DGND_24") (pintype "passive"))
      (node (ref "U10") (pin "25") (pinfunction "EP_25") (pintype "passive"))
      (node (ref "U10") (pin "4") (pinfunction "ADDR1_4") (pintype "passive"))
      (node (ref "U10") (pin "5") (pinfunction "ADDR0_5") (pintype "passive"))
      (node (ref "U11") (pin "4") (pinfunction "GND_4") (pintype "passive"))
      (node (ref "U12") (pin "12") (pinfunction "PGNDS_12") (pintype "passive"))
      (node (ref "U12") (pin "13") (pinfunction "PGNDS_13") (pintype "passive"))
      (node (ref "U12") (pin "18") (pinfunction "PGNDL_18") (pintype "passive"))
      (node (ref "U12") (pin "19") (pinfunction "PGNDL_19") (pintype "passive"))
      (node (ref "U12") (pin "25") (pinfunction "EP_25") (pintype "passive"))
      (node (ref "U12") (pin "7") (pinfunction "AGND_7") (pintype "passive"))
      (node (ref "U13") (pin "1") (pinfunction "ADDR2_1") (pintype "passive"))
      (node (ref "U13") (pin "12") (pinfunction "ENCOMP_12") (pintype "passive"))
      (node (ref "U13") (pin "16") (pinfunction "AVSS_16") (pintype "passive"))
      (node (ref "U13") (pin "18") (pinfunction "DVSS_18") (pintype "passive"))
      (node (ref "U13") (pin "24") (pinfunction "DGND_24") (pintype "passive"))
      (node (ref "U13") (pin "25") (pinfunction "EP_25") (pintype "passive"))
      (node (ref "U13") (pin "4") (pinfunction "ADDR1_4") (pintype "passive"))
      (node (ref "U13") (pin "5") (pinfunction "ADDR0_5") (pintype "passive"))
      (node (ref "U14") (pin "4") (pinfunction "GND_4") (pintype "passive"))
      (node (ref "U3") (pin "4") (pinfunction "GND_4") (pintype "power_in"))
      (node (ref "U4") (pin "17") (pinfunction "AGND_17") (pintype "power_in"))
      (node (ref "U4") (pin "18") (pinfunction "LADCOM_18") (pintype "passive"))
      (node (ref "U4") (pin "19") (pinfunction "IOUTB_19") (pintype "output"))
      (node (ref "U4") (pin "24") (pinfunction "DGND_24") (pintype "power_in"))
      (node (ref "U5") (pin "4") (pinfunction "GND_4") (pintype "power_in"))
      (node (ref "U7") (pin "17") (pinfunction "AGND_17") (pintype "power_in"))
      (node (ref "U7") (pin "18") (pinfunction "LADCOM_18") (pintype "passive"))
      (node (ref "U7") (pin "19") (pinfunction "IOUTB_19") (pintype "output"))
      (node (ref "U7") (pin "24") (pinfunction "DGND_24") (pintype "power_in"))
      (node (ref "U8") (pin "4") (pinfunction "GND_4") (pintype "power_in"))
    )
    (net (code "73") (name "GND") (class "Default")
      (node (ref "R14") (pin "2") (pinfunction "2_2") (pintype "passive"))
    )
    (net (code "74") (name "Net-(C33-Pad1)") (class "Default")
      (node (ref "C33") (pin "1") (pinfunction "1_1") (pintype "passive"))
      (node (ref "R35") (pin "1") (pinfunction "1_1") (pintype "passive"))
    )
    (net (code "75") (name "Net-(C37-Pad1)") (class "Default")
      (node (ref "C37") (pin "1") (pinfunction "1_1") (pintype "passive"))
      (node (ref "R37") (pin "1") (pinfunction "1_1") (pintype "passive"))
    )
    (net (code "76") (name "Net-(R33-Pad1)") (class "Default")
      (node (ref "R33") (pin "1") (pinfunction "1_1") (pintype "passive"))
      (node (ref "R40") (pin "1") (pinfunction "1_1") (pintype "passive"))
      (node (ref "U10") (pin "10") (pinfunction "IOUT_10") (pintype "passive"))
      (node (ref "U10") (pin "9") (pinfunction "IOUT_9") (pintype "passive"))
    )
    (net (code "77") (name "Net-(R45-Pad1)") (class "Default")
      (node (ref "R45") (pin "1") (pinfunction "1_1") (pintype "passive"))
      (node (ref "R50") (pin "1") (pinfunction "1_1") (pintype "passive"))
      (node (ref "U13") (pin "10") (pinfunction "IOUT_10") (pintype "passive"))
      (node (ref "U13") (pin "9") (pinfunction "IOUT_9") (pintype "passive"))
    )
    (net (code "78") (name "Net-(U1A-COMP1)") (class "Default")
      (node (ref "C3") (pin "1") (pinfunction "1_1") (pintype "passive"))
      (node (ref "U1") (pin "21") (pinfunction "COMP1_21") (pintype "passive"))
    )
    (net (code "79") (name "Net-(U1A-COMP2)") (class "Default")
      (node (ref "C4") (pin "1") (pinfunction "1_1") (pintype "passive"))
      (node (ref "U1") (pin "22") (pinfunction "COMP2_22") (pintype "passive"))
    )
    (net (code "80") (name "Net-(U1A-IOUTA)") (class "Default")
      (node (ref "C2") (pin "1") (pinfunction "1_1") (pintype "passive"))
      (node (ref "R7") (pin "1") (pinfunction "1_1") (pintype "passive"))
      (node (ref "U1") (pin "20") (pinfunction "IOUTA_20") (pintype "output"))
      (node (ref "U2") (pin "2") (pinfunction "IN1-_2") (pintype "input"))
    )
    (net (code "81") (name "Net-(U1A-IREFIN)") (class "Default")
      (node (ref "C8") (pin "2") (pinfunction "2_2") (pintype "passive"))
      (node (ref "R8") (pin "2") (pinfunction "2_2") (pintype "passive"))
      (node (ref "U1") (pin "16") (pinfunction "IREFIN_16") (pintype "input"))
    )
    (net (code "82") (name "Net-(U1A-REFOUT)") (class "Default")
      (node (ref "C1") (pin "1") (pinfunction "1_1") (pintype "passive"))
      (node (ref "U1") (pin "15") (pinfunction "REFOUT_15") (pintype "output"))
    )
    (net (code "83") (name "Net-(U2-IN1+)") (class "Default")
      (node (ref "R9") (pin "2") (pinfunction "2_2") (pintype "passive"))
      (node (ref "U2") (pin "3") (pinfunction "IN1+_3") (pintype "input"))
    )
    (net (code "84") (name "Net-(U2-IN2+)") (class "Default")
      (node (ref "C2") (pin "2") (pinfunction "2_2") (pintype "passive"))
      (node (ref "R7") (pin "2") (pinfunction "2_2") (pintype "passive"))
      (node (ref "U2") (pin "1") (pinfunction "VOUT1_1") (pintype "output"))
      (node (ref "U2") (pin "5") (pinfunction "IN2+_5") (pintype "input"))
    )
    (net (code "85") (name "Net-(U2-IN2-)") (class "Default")
      (node (ref "R12") (pin "1") (pinfunction "1_1") (pintype "passive"))
      (node (ref "U2") (pin "6") (pinfunction "IN2-_6") (pintype "input"))
      (node (ref "U2") (pin "7") (pinfunction "VOUT2_7") (pintype "output"))
    )
    (net (code "86") (name "Net-(U2-IN3+)") (class "Default")
      (node (ref "R12") (pin "2") (pinfunction "2_2") (pintype "passive"))
      (node (ref "R13") (pin "1") (pinfunction "1_1") (pintype "passive"))
      (node (ref "U2") (pin "10") (pinfunction "IN3+_10") (pintype "input"))
    )
    (net (code "87") (name "Net-(U2-IN3-)") (class "Default")
      (node (ref "R10") (pin "2") (pinfunction "2_2") (pintype "passive"))
      (node (ref "R6") (pin "1") (pinfunction "1_1") (pintype "passive"))
      (node (ref "U2") (pin "9") (pinfunction "IN3-_9") (pintype "input"))
    )
    (net (code "88") (name "Net-(U2-IN4-)") (class "Default")
      (node (ref "R13") (pin "2") (pinfunction "2_2") (pintype "passive"))
      (node (ref "U2") (pin "13") (pinfunction "IN4-_13") (pintype "input"))
      (node (ref "U2") (pin "14") (pinfunction "VOUT4_14") (pintype "output"))
    )
    (net (code "89") (name "Net-(U2-VOUT3)") (class "Default")
      (node (ref "R11") (pin "5") (pinfunction "5_5") (pintype "passive"))
      (node (ref "R11") (pin "6") (pinfunction "6_6") (pintype "passive"))
      (node (ref "R11") (pin "7") (pinfunction "7_7") (pintype "passive"))
      (node (ref "R11") (pin "8") (pinfunction "8_8") (pintype "passive"))
      (node (ref "R6") (pin "2") (pinfunction "2_2") (pintype "passive"))
      (node (ref "U2") (pin "8") (pinfunction "VOUT3_8") (pintype "output"))
    )
    (net (code "90") (name "Net-(U3-VOUT)") (class "Default")
      (node (ref "R8") (pin "1") (pinfunction "1_1") (pintype "passive"))
      (node (ref "U3") (pin "6") (pinfunction "VOUT_6") (pintype "output"))
    )
    (net (code "91") (name "Net-(U4A-COMP1)") (class "Default")
      (node (ref "C12") (pin "1") (pinfunction "1_1") (pintype "passive"))
      (node (ref "U4") (pin "21") (pinfunction "COMP1_21") (pintype "passive"))
    )
    (net (code "92") (name "Net-(U4A-COMP2)") (class "Default")
      (node (ref "C14") (pin "1") (pinfunction "1_1") (pintype "passive"))
      (node (ref "U4") (pin "22") (pinfunction "COMP2_22") (pintype "passive"))
    )
    (net (code "93") (name "Net-(U4A-IOUTA)") (class "Default")
      (node (ref "C13") (pin "1") (pinfunction "1_1") (pintype "passive"))
      (node (ref "R16") (pin "1") (pinfunction "1_1") (pintype "passive"))
      (node (ref "U4") (pin "20") (pinfunction "IOUTA_20") (pintype "output"))
      (node (ref "U6") (pin "2") (pinfunction "IN1-_2") (pintype "input"))
    )
    (net (code "94") (name "Net-(U4A-IREFIN)") (class "Default")
      (node (ref "C18") (pin "2") (pinfunction "2_2") (pintype "passive"))
      (node (ref "R17") (pin "2") (pinfunction "2_2") (pintype "passive"))
      (node (ref "U4") (pin "16") (pinfunction "IREFIN_16") (pintype "input"))
    )
    (net (code "95") (name "Net-(U4A-REFOUT)") (class "Default")
      (node (ref "C11") (pin "1") (pinfunction "1_1") (pintype "passive"))
      (node (ref "U4") (pin "15") (pinfunction "REFOUT_15") (pintype "output"))
    )
    (net (code "96") (name "Net-(U5-VOUT)") (class "Default")
      (node (ref "R17") (pin "1") (pinfunction "1_1") (pintype "passive"))
      (node (ref "U5") (pin "6") (pinfunction "VOUT_6") (pintype "output"))
    )
    (net (code "97") (name "Net-(U6-IN1+)") (class "Default")
      (node (ref "R18") (pin "2") (pinfunction "2_2") (pintype "passive"))
      (node (ref "U6") (pin "3") (pinfunction "IN1+_3") (pintype "input"))
    )
    (net (code "98") (name "Net-(U6-IN2+)") (class "Default")
      (node (ref "C13") (pin "2") (pinfunction "2_2") (pintype "passive"))
      (node (ref "R16") (pin "2") (pinfunction "2_2") (pintype "passive"))
      (node (ref "U6") (pin "1") (pinfunction "VOUT1_1") (pintype "output"))
      (node (ref "U6") (pin "5") (pinfunction "IN2+_5") (pintype "input"))
    )
    (net (code "99") (name "Net-(U6-IN2-)") (class "Default")
      (node (ref "R21") (pin "1") (pinfunction "1_1") (pintype "passive"))
      (node (ref "U6") (pin "6") (pinfunction "IN2-_6") (pintype "input"))
      (node (ref "U6") (pin "7") (pinfunction "VOUT2_7") (pintype "output"))
    )
    (net (code "100") (name "Net-(U6-IN3+)") (class "Default")
      (node (ref "R21") (pin "2") (pinfunction "2_2") (pintype "passive"))
      (node (ref "R22") (pin "1") (pinfunction "1_1") (pintype "passive"))
      (node (ref "U6") (pin "10") (pinfunction "IN3+_10") (pintype "input"))
    )
    (net (code "101") (name "Net-(U6-IN3-)") (class "Default")
      (node (ref "R15") (pin "1") (pinfunction "1_1") (pintype "passive"))
      (node (ref "R19") (pin "2") (pinfunction "2_2") (pintype "passive"))
      (node (ref "U6") (pin "9") (pinfunction "IN3-_9") (pintype "input"))
    )
    (net (code "102") (name "Net-(U6-IN4-)") (class "Default")
      (node (ref "R22") (pin "2") (pinfunction "2_2") (pintype "passive"))
      (node (ref "U6") (pin "13") (pinfunction "IN4-_13") (pintype "input"))
      (node (ref "U6") (pin "14") (pinfunction "VOUT4_14") (pintype "output"))
    )
    (net (code "103") (name "Net-(U6-VOUT3)") (class "Default")
      (node (ref "R15") (pin "2") (pinfunction "2_2") (pintype "passive"))
      (node (ref "R20") (pin "5") (pinfunction "5_5") (pintype "passive"))
      (node (ref "R20") (pin "6") (pinfunction "6_6") (pintype "passive"))
      (node (ref "R20") (pin "7") (pinfunction "7_7") (pintype "passive"))
      (node (ref "R20") (pin "8") (pinfunction "8_8") (pintype "passive"))
      (node (ref "U6") (pin "8") (pinfunction "VOUT3_8") (pintype "output"))
    )
    (net (code "104") (name "Net-(U7A-COMP1)") (class "Default")
      (node (ref "C22") (pin "1") (pinfunction "1_1") (pintype "passive"))
      (node (ref "U7") (pin "21") (pinfunction "COMP1_21") (pintype "passive"))
    )
    (net (code "105") (name "Net-(U7A-COMP2)") (class "Default")
      (node (ref "C23") (pin "1") (pinfunction "1_1") (pintype "passive"))
      (node (ref "U7") (pin "22") (pinfunction "COMP2_22") (pintype "passive"))
    )
    (net (code "106") (name "Net-(U7A-IOUTA)") (class "Default")
      (node (ref "C24") (pin "1") (pinfunction "1_1") (pintype "passive"))
      (node (ref "R24") (pin "1") (pinfunction "1_1") (pintype "passive"))
      (node (ref "U7") (pin "20") (pinfunction "IOUTA_20") (pintype "output"))
      (node (ref "U9") (pin "2") (pinfunction "IN1-_2") (pintype "input"))
    )
    (net (code "107") (name "Net-(U7A-IREFIN)") (class "Default")
      (node (ref "C28") (pin "2") (pinfunction "2_2") (pintype "passive"))
      (node (ref "R25") (pin "2") (pinfunction "2_2") (pintype "passive"))
      (node (ref "U7") (pin "16") (pinfunction "IREFIN_16") (pintype "input"))
    )
    (net (code "108") (name "Net-(U7A-REFOUT)") (class "Default")
      (node (ref "C21") (pin "1") (pinfunction "1_1") (pintype "passive"))
      (node (ref "U7") (pin "15") (pinfunction "REFOUT_15") (pintype "output"))
    )
    (net (code "109") (name "Net-(U8-VOUT)") (class "Default")
      (node (ref "R25") (pin "1") (pinfunction "1_1") (pintype "passive"))
      (node (ref "U8") (pin "6") (pinfunction "VOUT_6") (pintype "output"))
    )
    (net (code "110") (name "Net-(U9-IN1+)") (class "Default")
      (node (ref "R26") (pin "2") (pinfunction "2_2") (pintype "passive"))
      (node (ref "U9") (pin "3") (pinfunction "IN1+_3") (pintype "input"))
    )
    (net (code "111") (name "Net-(U9-IN2+)") (class "Default")
      (node (ref "C24") (pin "2") (pinfunction "2_2") (pintype "passive"))
      (node (ref "R24") (pin "2") (pinfunction "2_2") (pintype "passive"))
      (node (ref "U9") (pin "1") (pinfunction "VOUT1_1") (pintype "output"))
      (node (ref "U9") (pin "5") (pinfunction "IN2+_5") (pintype "input"))
    )
    (net (code "112") (name "Net-(U9-IN2-)") (class "Default")
      (node (ref "R29") (pin "1") (pinfunction "1_1") (pintype "passive"))
      (node (ref "U9") (pin "6") (pinfunction "IN2-_6") (pintype "input"))
      (node (ref "U9") (pin "7") (pinfunction "VOUT2_7") (pintype "output"))
    )
    (net (code "113") (name "Net-(U9-IN3+)") (class "Default")
      (node (ref "R29") (pin "2") (pinfunction "2_2") (pintype "passive"))
      (node (ref "R30") (pin "1") (pinfunction "1_1") (pintype "passive"))
      (node (ref "U9") (pin "10") (pinfunction "IN3+_10") (pintype "input"))
    )
    (net (code "114") (name "Net-(U9-IN3-)") (class "Default")
      (node (ref "R23") (pin "1") (pinfunction "1_1") (pintype "passive"))
      (node (ref "R27") (pin "2") (pinfunction "2_2") (pintype "passive"))
      (node (ref "U9") (pin "9") (pinfunction "IN3-_9") (pintype "input"))
    )
    (net (code "115") (name "Net-(U9-IN4-)") (class "Default")
      (node (ref "R30") (pin "2") (pinfunction "2_2") (pintype "passive"))
      (node (ref "U9") (pin "13") (pinfunction "IN4-_13") (pintype "input"))
      (node (ref "U9") (pin "14") (pinfunction "VOUT4_14") (pintype "output"))
    )
    (net (code "116") (name "Net-(U9-VOUT3)") (class "Default")
      (node (ref "R23") (pin "2") (pinfunction "2_2") (pintype "passive"))
      (node (ref "R28") (pin "5") (pinfunction "5_5") (pintype "passive"))
      (node (ref "R28") (pin "6") (pinfunction "6_6") (pintype "passive"))
      (node (ref "R28") (pin "7") (pinfunction "7_7") (pintype "passive"))
      (node (ref "R28") (pin "8") (pinfunction "8_8") (pintype "passive"))
      (node (ref "U9") (pin "8") (pinfunction "VOUT3_8") (pintype "output"))
    )
    (net (code "117") (name "Net-(U10A-RSN)") (class "Default")
      (node (ref "R40") (pin "2") (pinfunction "2_2") (pintype "passive"))
      (node (ref "U10") (pin "2") (pinfunction "RSN_2") (pintype "passive"))
    )
    (net (code "118") (name "Net-(U10B-DVDD)") (class "Default")
      (node (ref "C31") (pin "1") (pinfunction "1_1") (pintype "passive"))
      (node (ref "L1") (pin "2") (pinfunction "2_2") (pintype "passive"))
      (node (ref "U10") (pin "23") (pinfunction "DVDD_23") (pintype "power_in"))
    )
    (net (code "119") (name "Net-(U10B-VREF)") (class "Default")
      (node (ref "C39") (pin "2") (pinfunction "2_2") (pintype "passive"))
      (node (ref "U10") (pin "14") (pinfunction "VREF_14") (pintype "passive"))
      (node (ref "U11") (pin "6") (pinfunction "VOUT_6") (pintype "passive"))
    )
    (net (code "120") (name "Net-(U12A-EN_S{slash}Y)") (class "Default")
      (node (ref "R44") (pin "2") (pinfunction "2_2") (pintype "passive"))
      (node (ref "U12") (pin "8") (pinfunction "EN_S/Y_8") (pintype "passive"))
    )
    (net (code "121") (name "Net-(U12A-ILIM)") (class "Default")
      (node (ref "R43") (pin "1") (pinfunction "1_1") (pintype "passive"))
      (node (ref "R48") (pin "2") (pinfunction "2_2") (pintype "passive"))
      (node (ref "U12") (pin "4") (pinfunction "ILIM_4") (pintype "passive"))
    )
    (net (code "122") (name "Net-(U12A-IN1N)") (class "Default")
      (node (ref "R39") (pin "2") (pinfunction "2_2") (pintype "passive"))
      (node (ref "R41") (pin "2") (pinfunction "2_2") (pintype "passive"))
      (node (ref "R42") (pin "1") (pinfunction "1_1") (pintype "passive"))
      (node (ref "U12") (pin "22") (pinfunction "IN1N_22") (pintype "passive"))
    )
    (net (code "123") (name "Net-(U12A-IN1P)") (class "Default")
      (node (ref "R34") (pin "2") (pinfunction "2_2") (pintype "passive"))
      (node (ref "R36") (pin "2") (pinfunction "2_2") (pintype "passive"))
      (node (ref "U12") (pin "23") (pinfunction "IN1P_23") (pintype "passive"))
    )
    (net (code "124") (name "Net-(U12A-IN2N)") (class "Default")
      (node (ref "C32") (pin "1") (pinfunction "1_1") (pintype "passive"))
      (node (ref "C33") (pin "2") (pinfunction "2_2") (pintype "passive"))
      (node (ref "R37") (pin "2") (pinfunction "2_2") (pintype "passive"))
      (node (ref "R38") (pin "1") (pinfunction "1_1") (pintype "passive"))
      (node (ref "U12") (pin "1") (pinfunction "IN2N_1") (pintype "passive"))
    )
    (net (code "125") (name "Net-(U12A-IN2P)") (class "Default")
      (node (ref "R31") (pin "2") (pinfunction "2_2") (pintype "passive"))
      (node (ref "R32") (pin "2") (pinfunction "2_2") (pintype "passive"))
      (node (ref "U12") (pin "24") (pinfunction "IN2P_24") (pintype "passive"))
    )
    (net (code "126") (name "Net-(U12A-OUT1)") (class "Default")
      (node (ref "R35") (pin "2") (pinfunction "2_2") (pintype "passive"))
      (node (ref "R38") (pin "2") (pinfunction "2_2") (pintype "passive"))
      (node (ref "R42") (pin "2") (pinfunction "2_2") (pintype "passive"))
      (node (ref "U12") (pin "21") (pinfunction "OUT1_21") (pintype "passive"))
    )
    (net (code "127") (name "Net-(U12A-OUT2)") (class "Default")
      (node (ref "C32") (pin "2") (pinfunction "2_2") (pintype "passive"))
      (node (ref "C37") (pin "2") (pinfunction "2_2") (pintype "passive"))
      (node (ref "U12") (pin "2") (pinfunction "OUT2_2") (pintype "passive"))
    )
    (net (code "128") (name "Net-(U12A-SFB)") (class "Default")
      (node (ref "R47") (pin "2") (pinfunction "2_2") (pintype "passive"))
      (node (ref "U12") (pin "10") (pinfunction "SFB_10") (pintype "passive"))
    )
    (net (code "129") (name "Net-(U12A-SW)") (class "Default")
      (node (ref "L3") (pin "2") (pinfunction "2_2") (pintype "passive"))
      (node (ref "U12") (pin "14") (pinfunction "SW_14") (pintype "passive"))
    )
    (net (code "130") (name "Net-(U12A-VLIM{slash}SD)") (class "Default")
      (node (ref "R46") (pin "1") (pinfunction "1_1") (pintype "passive"))
      (node (ref "R49") (pin "2") (pinfunction "2_2") (pintype "passive"))
      (node (ref "U12") (pin "3") (pinfunction "VLIM/SD_3") (pintype "passive"))
    )
    (net (code "131") (name "Net-(U13A-RSN)") (class "Default")
      (node (ref "R50") (pin "2") (pinfunction "2_2") (pintype "passive"))
      (node (ref "U13") (pin "2") (pinfunction "RSN_2") (pintype "passive"))
    )
    (net (code "132") (name "Net-(U13B-DVDD)") (class "Default")
      (node (ref "C42") (pin "1") (pinfunction "1_1") (pintype "passive"))
      (node (ref "L2") (pin "2") (pinfunction "2_2") (pintype "passive"))
      (node (ref "U13") (pin "23") (pinfunction "DVDD_23") (pintype "power_in"))
    )
    (net (code "133") (name "Net-(U13B-VREF)") (class "Default")
      (node (ref "C50") (pin "2") (pinfunction "2_2") (pintype "passive"))
      (node (ref "U13") (pin "14") (pinfunction "VREF_14") (pintype "passive"))
      (node (ref "U14") (pin "6") (pinfunction "VOUT_6") (pintype "passive"))
    )
    (net (code "134") (name "unconnected-(S7500-NC-Pad8)") (class "Default")
      (node (ref "S7500") (pin "8") (pinfunction "NC_8") (pintype "passive+no_connect"))
    )
    (net (code "135") (name "unconnected-(S7500-PD,ref-Pad7)") (class "Default")
      (node (ref "S7500") (pin "7") (pinfunction "PD,ref_7") (pintype "passive+no_connect"))
    )
    (net (code "136") (name "unconnected-(S7500-PD,λ-Pad6)") (class "Default")
      (node (ref "S7500") (pin "6") (pinfunction "PD,λ_6") (pintype "passive+no_connect"))
    )
    (net (code "137") (name "unconnected-(S7500-Pad15)") (class "Default")
      (node (ref "S7500") (pin "15") (pinfunction "15_15") (pintype "passive+no_connect"))
    )
    (net (code "138") (name "unconnected-(S7500-Pad16)") (class "Default")
      (node (ref "S7500") (pin "16") (pinfunction "16_16") (pintype "passive+no_connect"))
    )
    (net (code "139") (name "unconnected-(S7500-Pad17)") (class "Default")
      (node (ref "S7500") (pin "17") (pinfunction "17_17") (pintype "passive+no_connect"))
    )
    (net (code "140") (name "unconnected-(S7500-Pad18)") (class "Default")
      (node (ref "S7500") (pin "18") (pinfunction "18_18") (pintype "passive+no_connect"))
    )
    (net (code "141") (name "unconnected-(S7500-Pad19)") (class "Default")
      (node (ref "S7500") (pin "19") (pinfunction "19_19") (pintype "passive+no_connect"))
    )
    (net (code "142") (name "unconnected-(S7500-Pad20)") (class "Default")
      (node (ref "S7500") (pin "20") (pinfunction "20_20") (pintype "passive+no_connect"))
    )
    (net (code "143") (name "unconnected-(S7500-Pad21)") (class "Default")
      (node (ref "S7500") (pin "21") (pinfunction "21_21") (pintype "passive+no_connect"))
    )
    (net (code "144") (name "unconnected-(S7500-nc-Pad4)") (class "Default")
      (node (ref "S7500") (pin "4") (pinfunction "nc_4") (pintype "passive+no_connect"))
    )
    (net (code "145") (name "unconnected-(U3-NC-Pad1)") (class "Default")
      (node (ref "U3") (pin "1") (pinfunction "NC_1") (pintype "passive+no_connect"))
    )
    (net (code "146") (name "unconnected-(U3-NC-Pad3)") (class "Default")
      (node (ref "U3") (pin "3") (pinfunction "NC_3") (pintype "passive+no_connect"))
    )
    (net (code "147") (name "unconnected-(U3-NC-Pad5)") (class "Default")
      (node (ref "U3") (pin "5") (pinfunction "NC_5") (pintype "passive+no_connect"))
    )
    (net (code "148") (name "unconnected-(U3-NC-Pad7)") (class "Default")
      (node (ref "U3") (pin "7") (pinfunction "NC_7") (pintype "passive+no_connect"))
    )
    (net (code "149") (name "unconnected-(U3-TP-Pad8)") (class "Default")
      (node (ref "U3") (pin "8") (pinfunction "TP_8") (pintype "passive+no_connect"))
    )
    (net (code "150") (name "unconnected-(U5-NC-Pad1)") (class "Default")
      (node (ref "U5") (pin "1") (pinfunction "NC_1") (pintype "passive+no_connect"))
    )
    (net (code "151") (name "unconnected-(U5-NC-Pad3)") (class "Default")
      (node (ref "U5") (pin "3") (pinfunction "NC_3") (pintype "passive+no_connect"))
    )
    (net (code "152") (name "unconnected-(U5-NC-Pad5)") (class "Default")
      (node (ref "U5") (pin "5") (pinfunction "NC_5") (pintype "passive+no_connect"))
    )
    (net (code "153") (name "unconnected-(U5-NC-Pad7)") (class "Default")
      (node (ref "U5") (pin "7") (pinfunction "NC_7") (pintype "passive+no_connect"))
    )
    (net (code "154") (name "unconnected-(U5-TP-Pad8)") (class "Default")
      (node (ref "U5") (pin "8") (pinfunction "TP_8") (pintype "passive+no_connect"))
    )
    (net (code "155") (name "unconnected-(U8-NC-Pad1)") (class "Default")
      (node (ref "U8") (pin "1") (pinfunction "NC_1") (pintype "passive+no_connect"))
    )
    (net (code "156") (name "unconnected-(U8-NC-Pad3)") (class "Default")
      (node (ref "U8") (pin "3") (pinfunction "NC_3") (pintype "passive+no_connect"))
    )
    (net (code "157") (name "unconnected-(U8-NC-Pad5)") (class "Default")
      (node (ref "U8") (pin "5") (pinfunction "NC_5") (pintype "passive+no_connect"))
    )
    (net (code "158") (name "unconnected-(U8-NC-Pad7)") (class "Default")
      (node (ref "U8") (pin "7") (pinfunction "NC_7") (pintype "passive+no_connect"))
    )
    (net (code "159") (name "unconnected-(U8-TP-Pad8)") (class "Default")
      (node (ref "U8") (pin "8") (pinfunction "TP_8") (pintype "passive+no_connect"))
    )
    (net (code "160") (name "unconnected-(U10A-FAULT-Pad6)") (class "Default")
      (node (ref "U10") (pin "6") (pinfunction "FAULT_6") (pintype "passive+no_connect"))
    )
    (net (code "161") (name "unconnected-(U10B-NC-Pad13)") (class "Default")
      (node (ref "U10") (pin "13") (pinfunction "NC_13") (pintype "passive+no_connect"))
    )
    (net (code "162") (name "unconnected-(U10B-NC-Pad17)") (class "Default")
      (node (ref "U10") (pin "17") (pinfunction "NC_17") (pintype "passive+no_connect"))
    )
    (net (code "163") (name "unconnected-(U11-NC-Pad1)") (class "Default")
      (node (ref "U11") (pin "1") (pinfunction "NC_1") (pintype "passive+no_connect"))
    )
    (net (code "164") (name "unconnected-(U11-NC-Pad3)") (class "Default")
      (node (ref "U11") (pin "3") (pinfunction "NC_3") (pintype "passive+no_connect"))
    )
    (net (code "165") (name "unconnected-(U11-NC-Pad5)") (class "Default")
      (node (ref "U11") (pin "5") (pinfunction "NC_5") (pintype "passive+no_connect"))
    )
    (net (code "166") (name "unconnected-(U11-NC-Pad7)") (class "Default")
      (node (ref "U11") (pin "7") (pinfunction "NC_7") (pintype "passive+no_connect"))
    )
    (net (code "167") (name "unconnected-(U11-NC-Pad8)") (class "Default")
      (node (ref "U11") (pin "8") (pinfunction "NC_8") (pintype "passive+no_connect"))
    )
    (net (code "168") (name "unconnected-(U12A-TI_EC-Pad11)") (class "Default")
      (node (ref "U12") (pin "11") (pinfunction "TI_EC_11") (pintype "passive+no_connect"))
    )
    (net (code "169") (name "unconnected-(U12A-TMPGD-Pad20)") (class "Default")
      (node (ref "U12") (pin "20") (pinfunction "TMPGD_20") (pintype "passive+no_connect"))
    )
    (net (code "170") (name "unconnected-(U12A-VTEC-Pad9)") (class "Default")
      (node (ref "U12") (pin "9") (pinfunction "VTEC_9") (pintype "passive+no_connect"))
    )
    (net (code "171") (name "unconnected-(U13A-FAULT-Pad6)") (class "Default")
      (node (ref "U13") (pin "6") (pinfunction "FAULT_6") (pintype "passive+no_connect"))
    )
    (net (code "172") (name "unconnected-(U13B-NC-Pad13)") (class "Default")
      (node (ref "U13") (pin "13") (pinfunction "NC_13") (pintype "passive+no_connect"))
    )
    (net (code "173") (name "unconnected-(U13B-NC-Pad17)") (class "Default")
      (node (ref "U13") (pin "17") (pinfunction "NC_17") (pintype "passive+no_connect"))
    )
    (net (code "174") (name "unconnected-(U14-NC-Pad1)") (class "Default")
      (node (ref "U14") (pin "1") (pinfunction "NC_1") (pintype "passive+no_connect"))
    )
    (net (code "175") (name "unconnected-(U14-NC-Pad3)") (class "Default")
      (node (ref "U14") (pin "3") (pinfunction "NC_3") (pintype "passive+no_connect"))
    )
    (net (code "176") (name "unconnected-(U14-NC-Pad5)") (class "Default")
      (node (ref "U14") (pin "5") (pinfunction "NC_5") (pintype "passive+no_connect"))
    )
    (net (code "177") (name "unconnected-(U14-NC-Pad7)") (class "Default")
      (node (ref "U14") (pin "7") (pinfunction "NC_7") (pintype "passive+no_connect"))
    )
    (net (code "178") (name "unconnected-(U14-NC-Pad8)") (class "Default")
      (node (ref "U14") (pin "8") (pinfunction "NC_8") (pintype "passive+no_connect"))
    )
  )
)
